# Aquila-2018_-.net
KiCad netlist of a schematic drawn in EAGLE
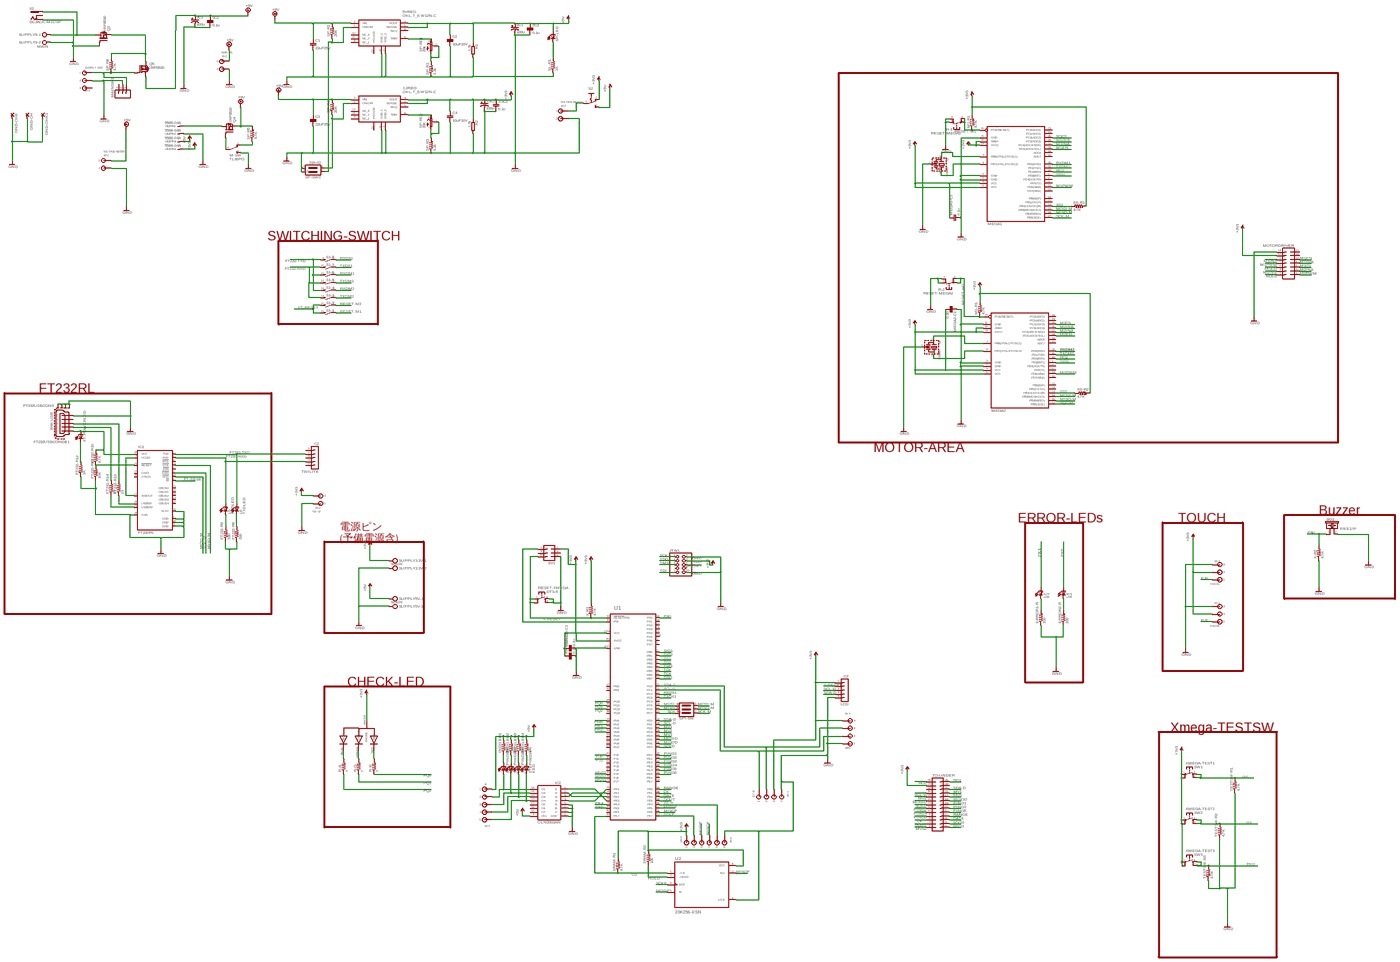
[diagram p0: schematic, sheet 1, overview]
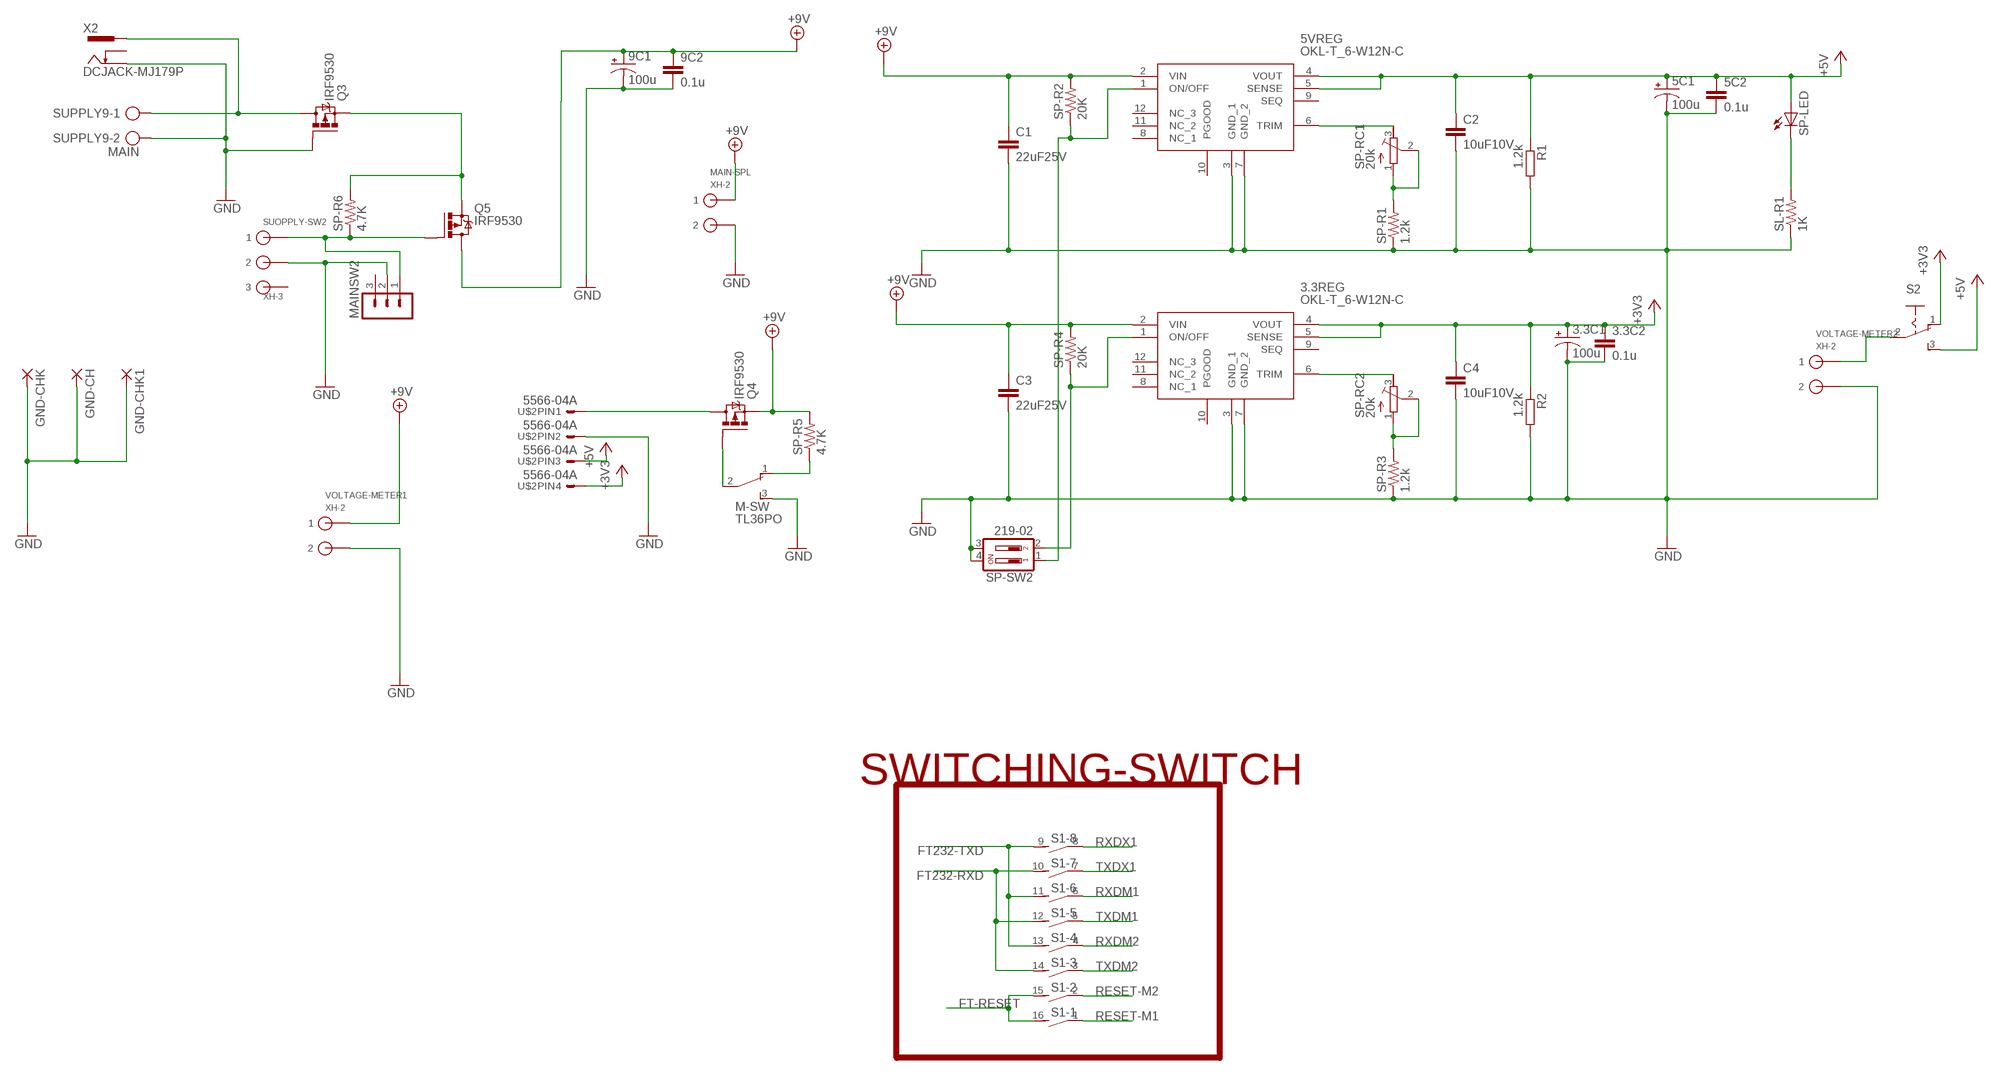
[diagram p1: schematic, sheet 1, part 1 of 5]
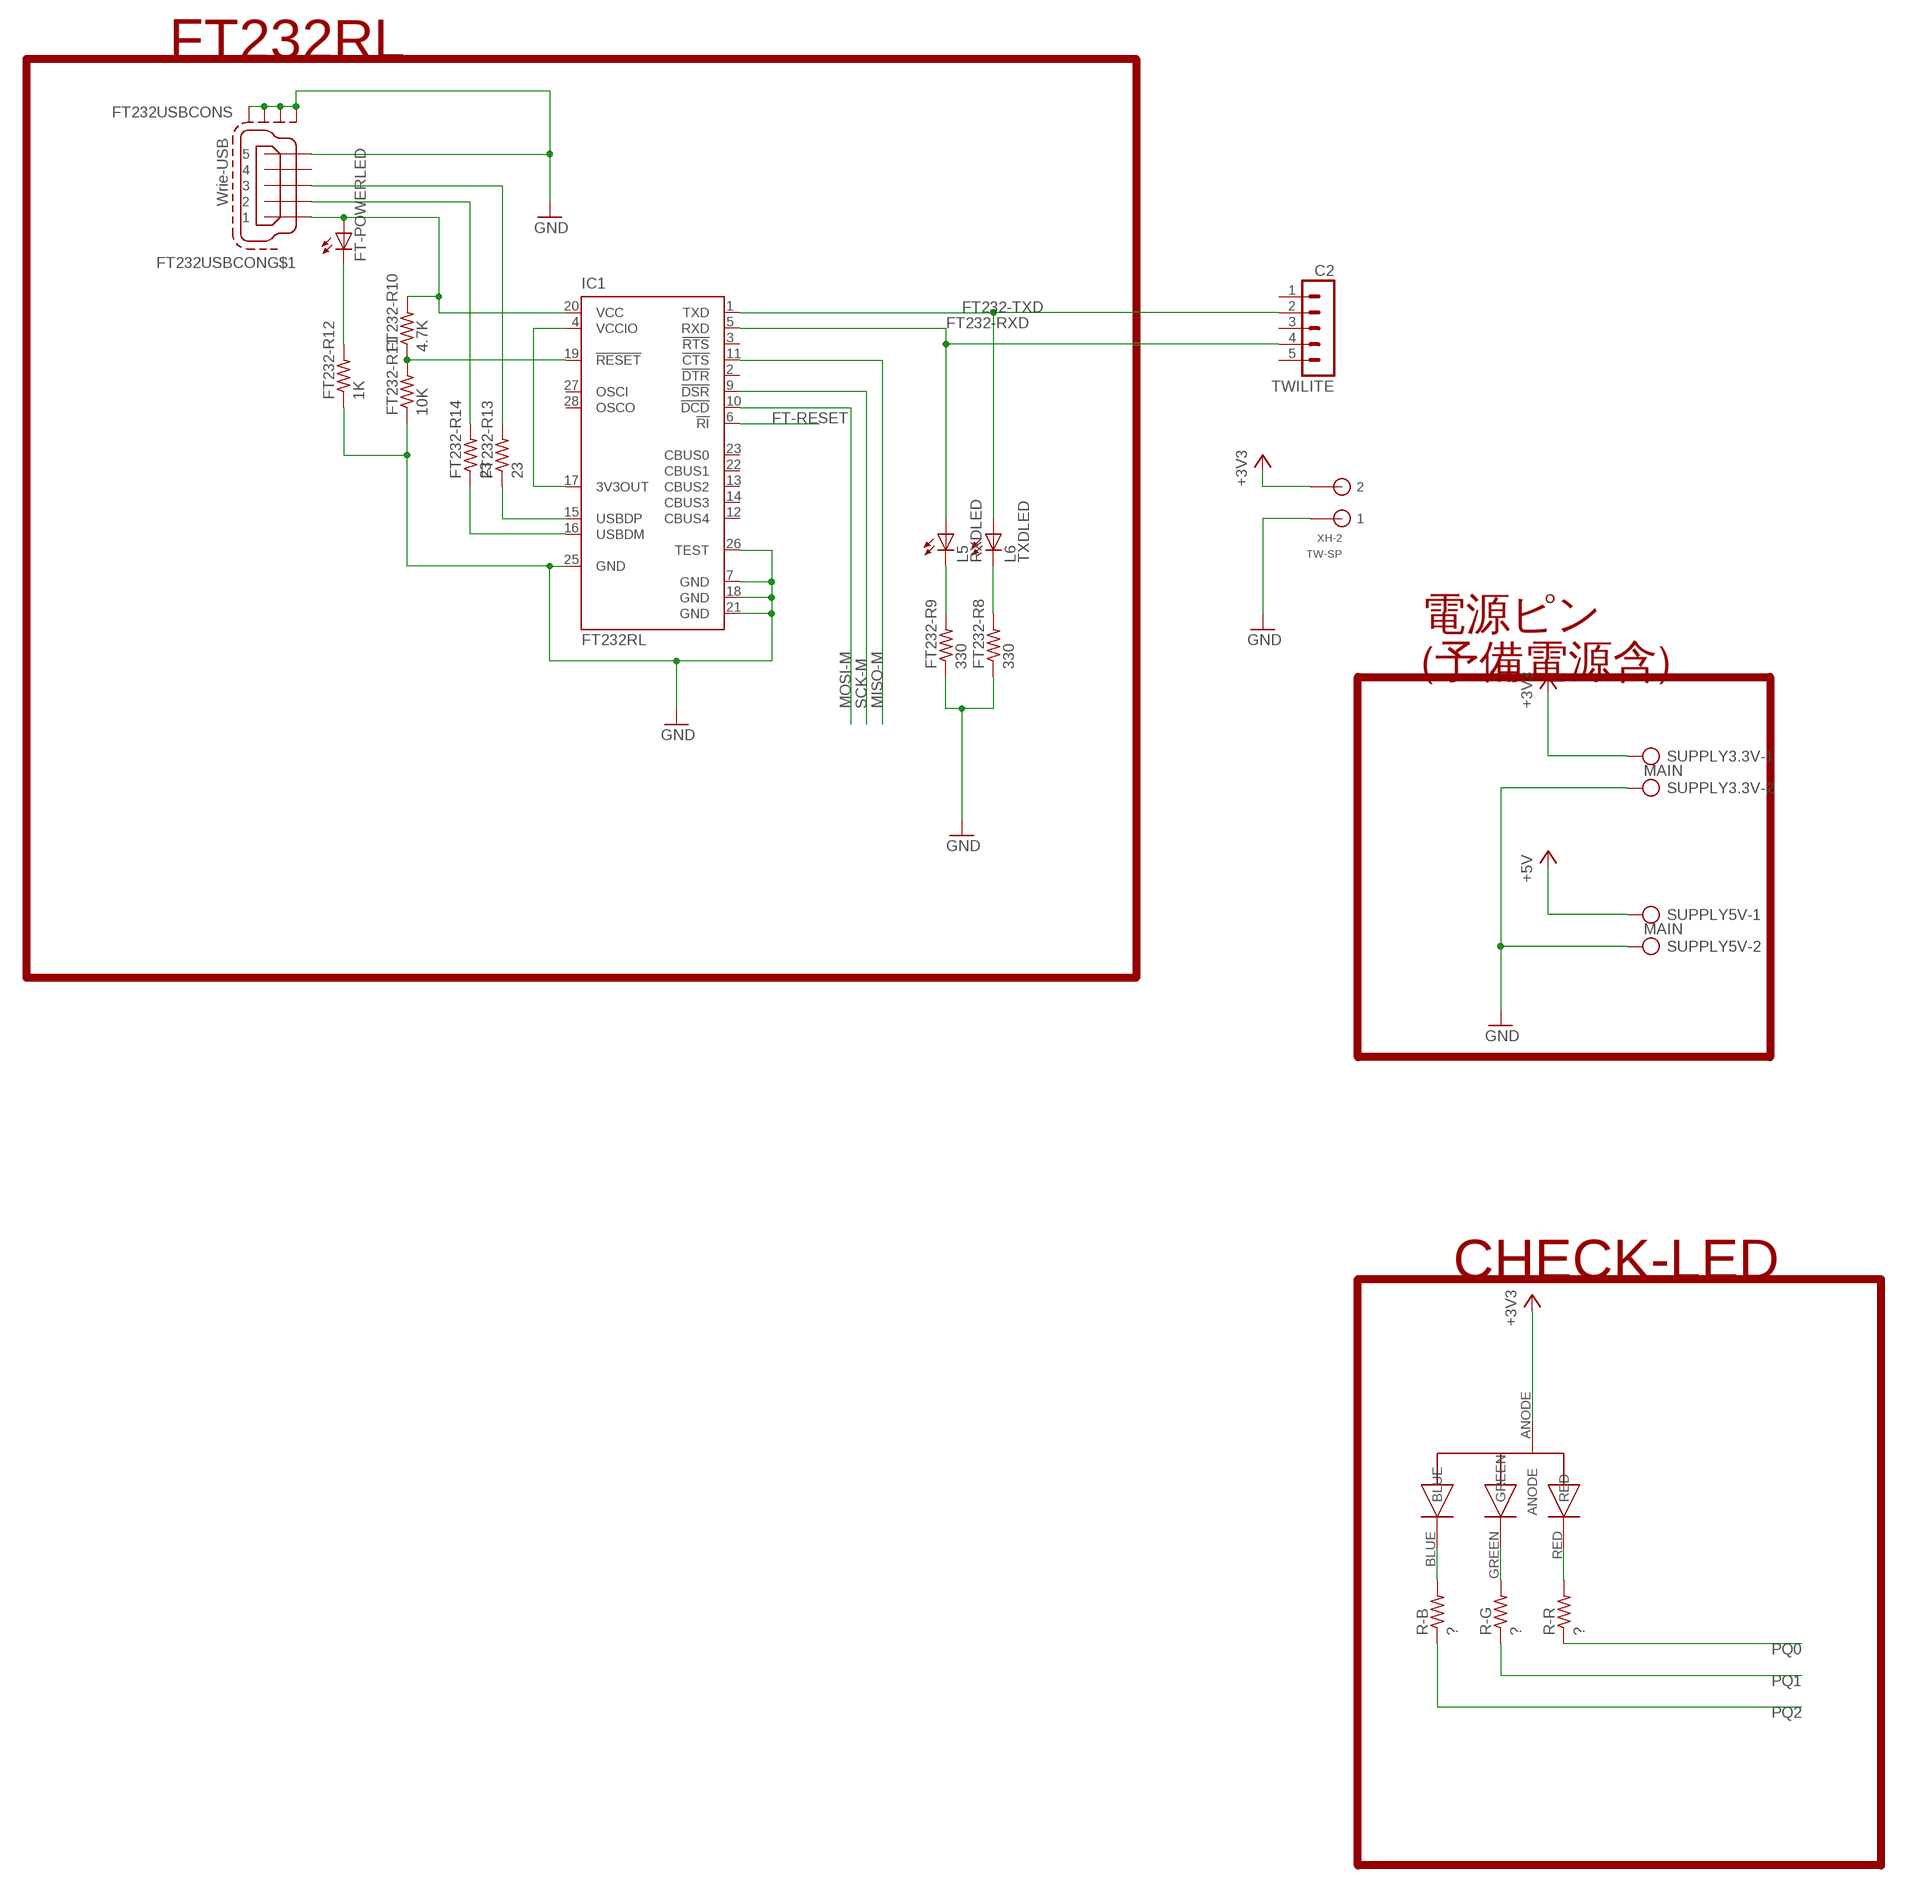
[diagram p2: schematic, sheet 1, part 2 of 5]
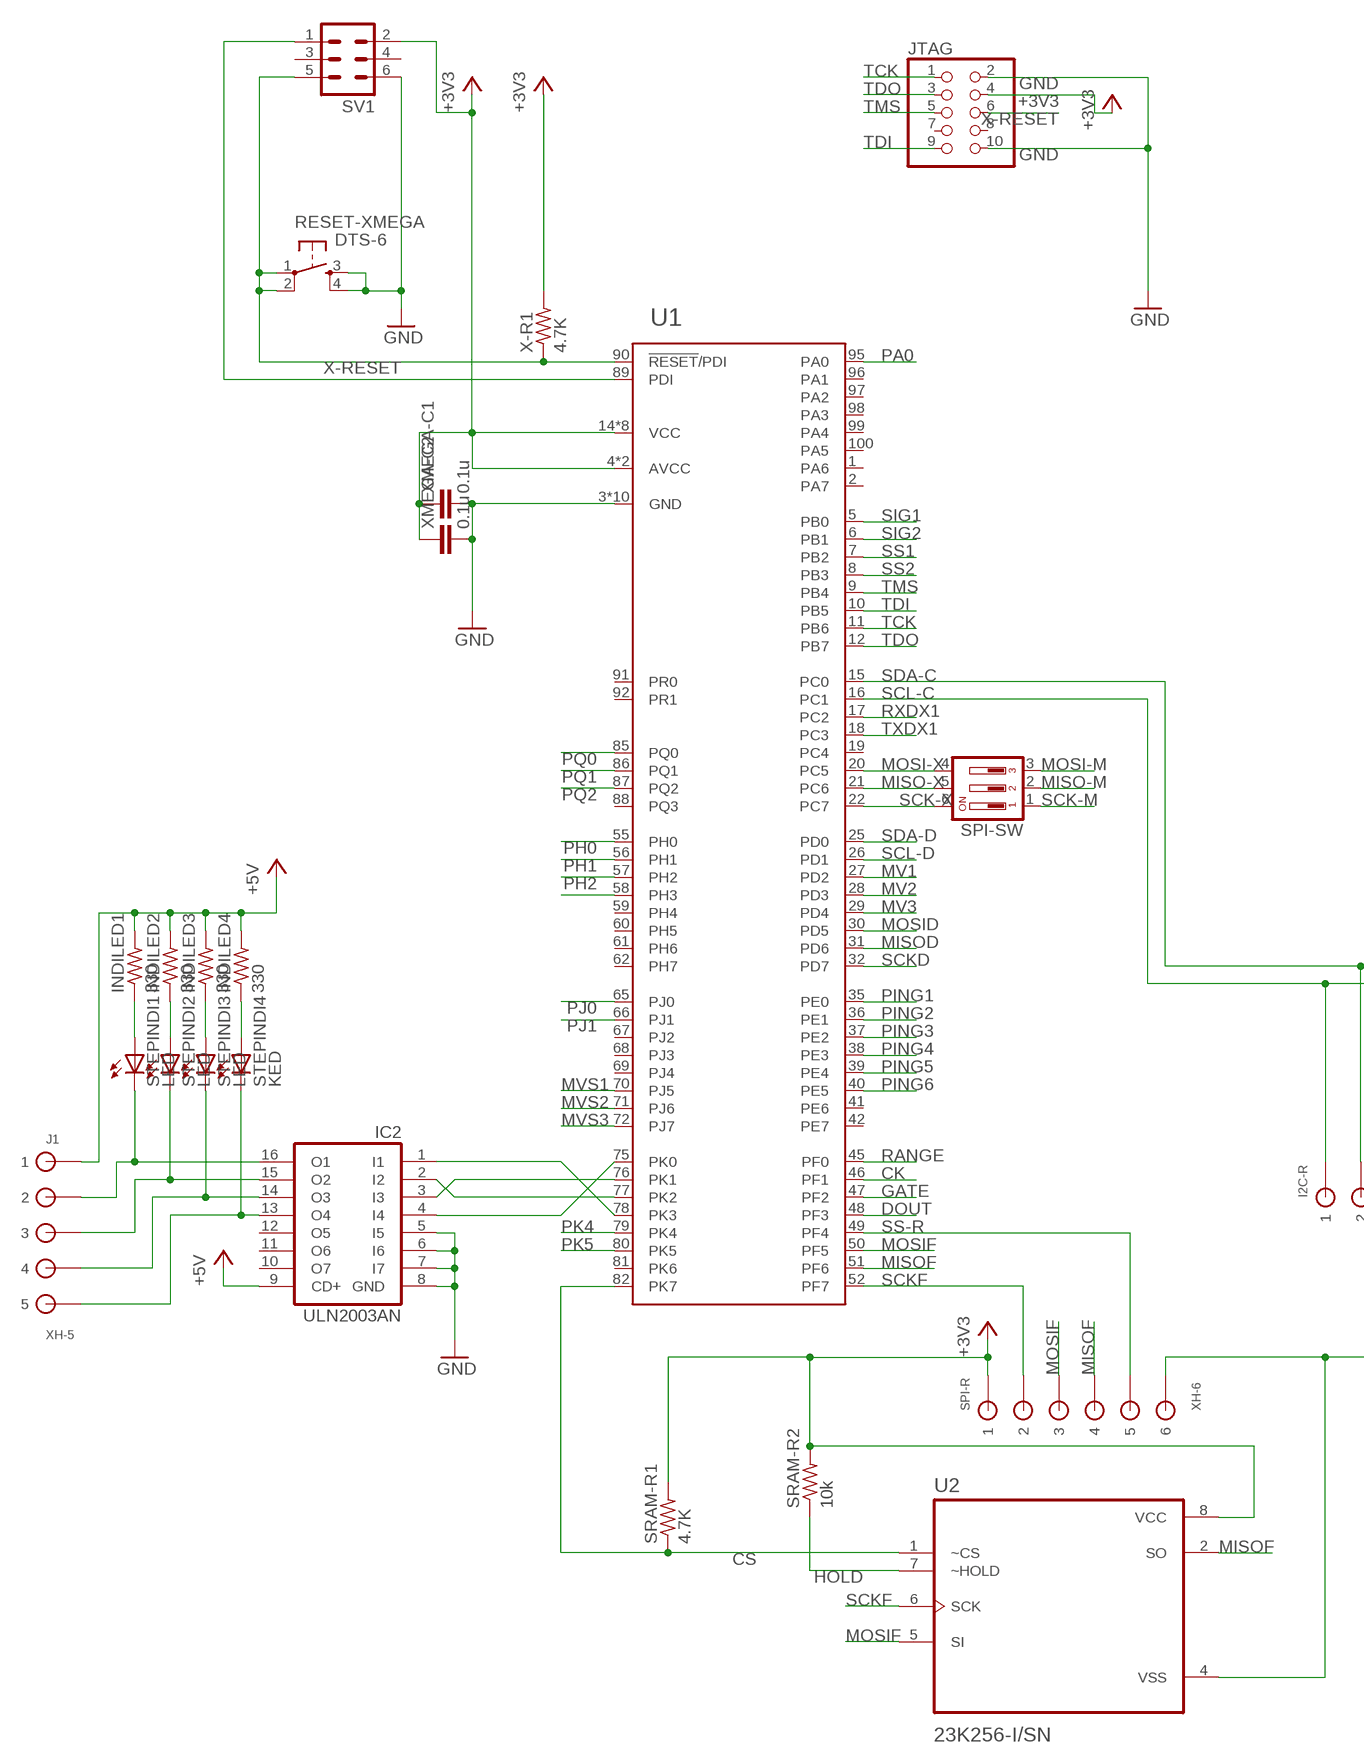
[diagram p3: schematic, sheet 1, part 3 of 5]
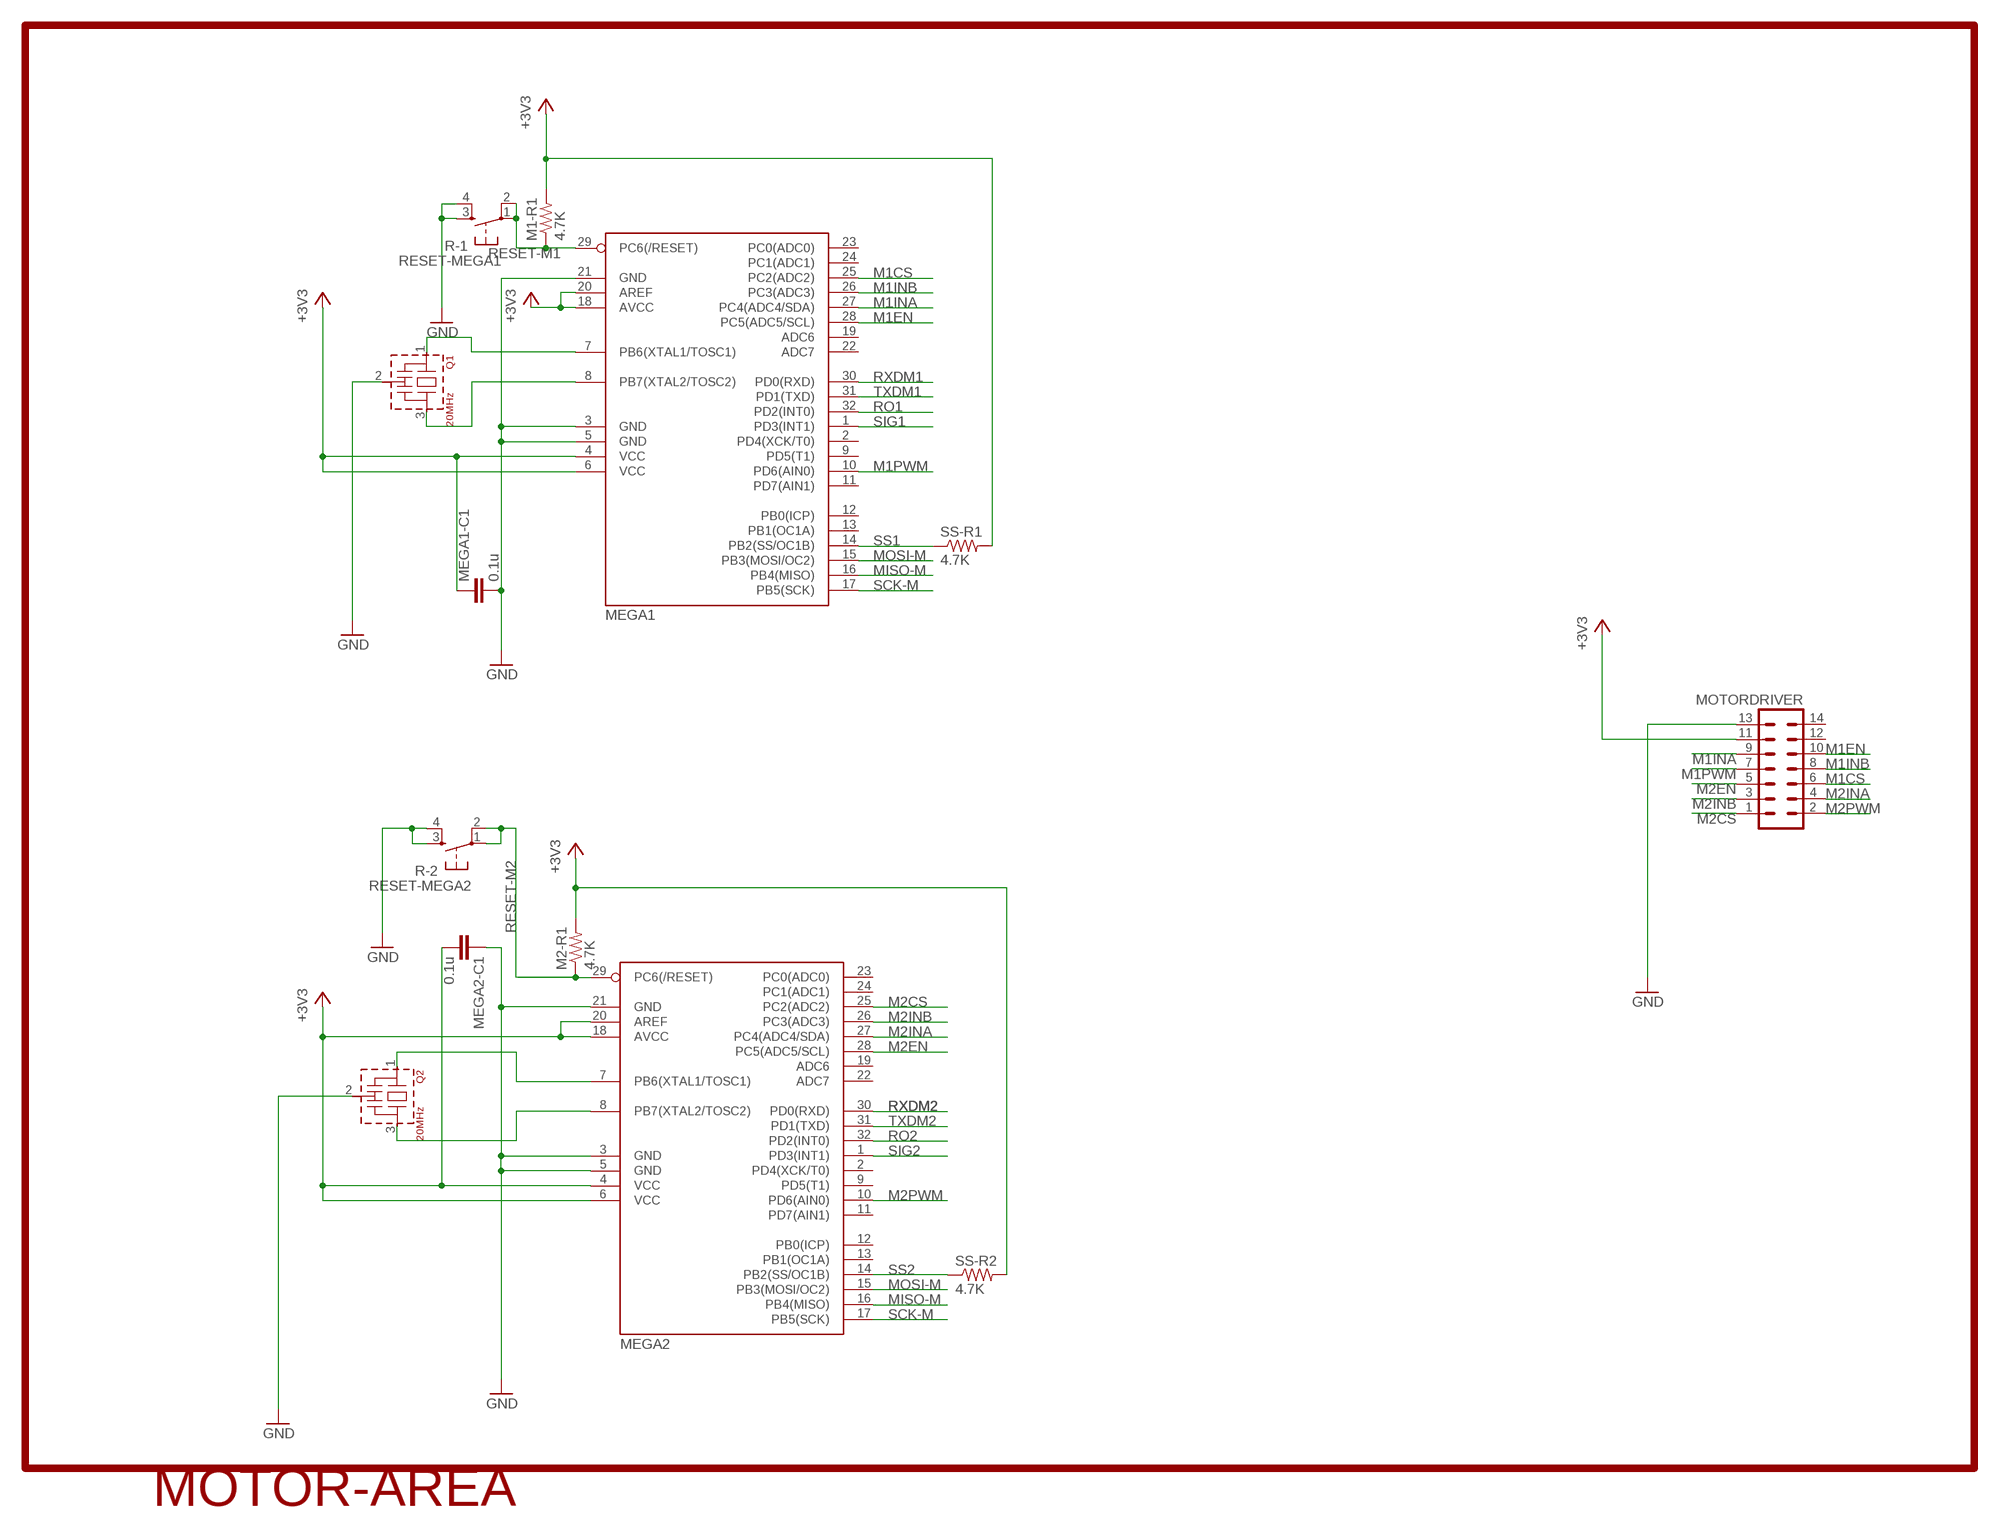
[diagram p4: schematic, sheet 1, part 4 of 5]
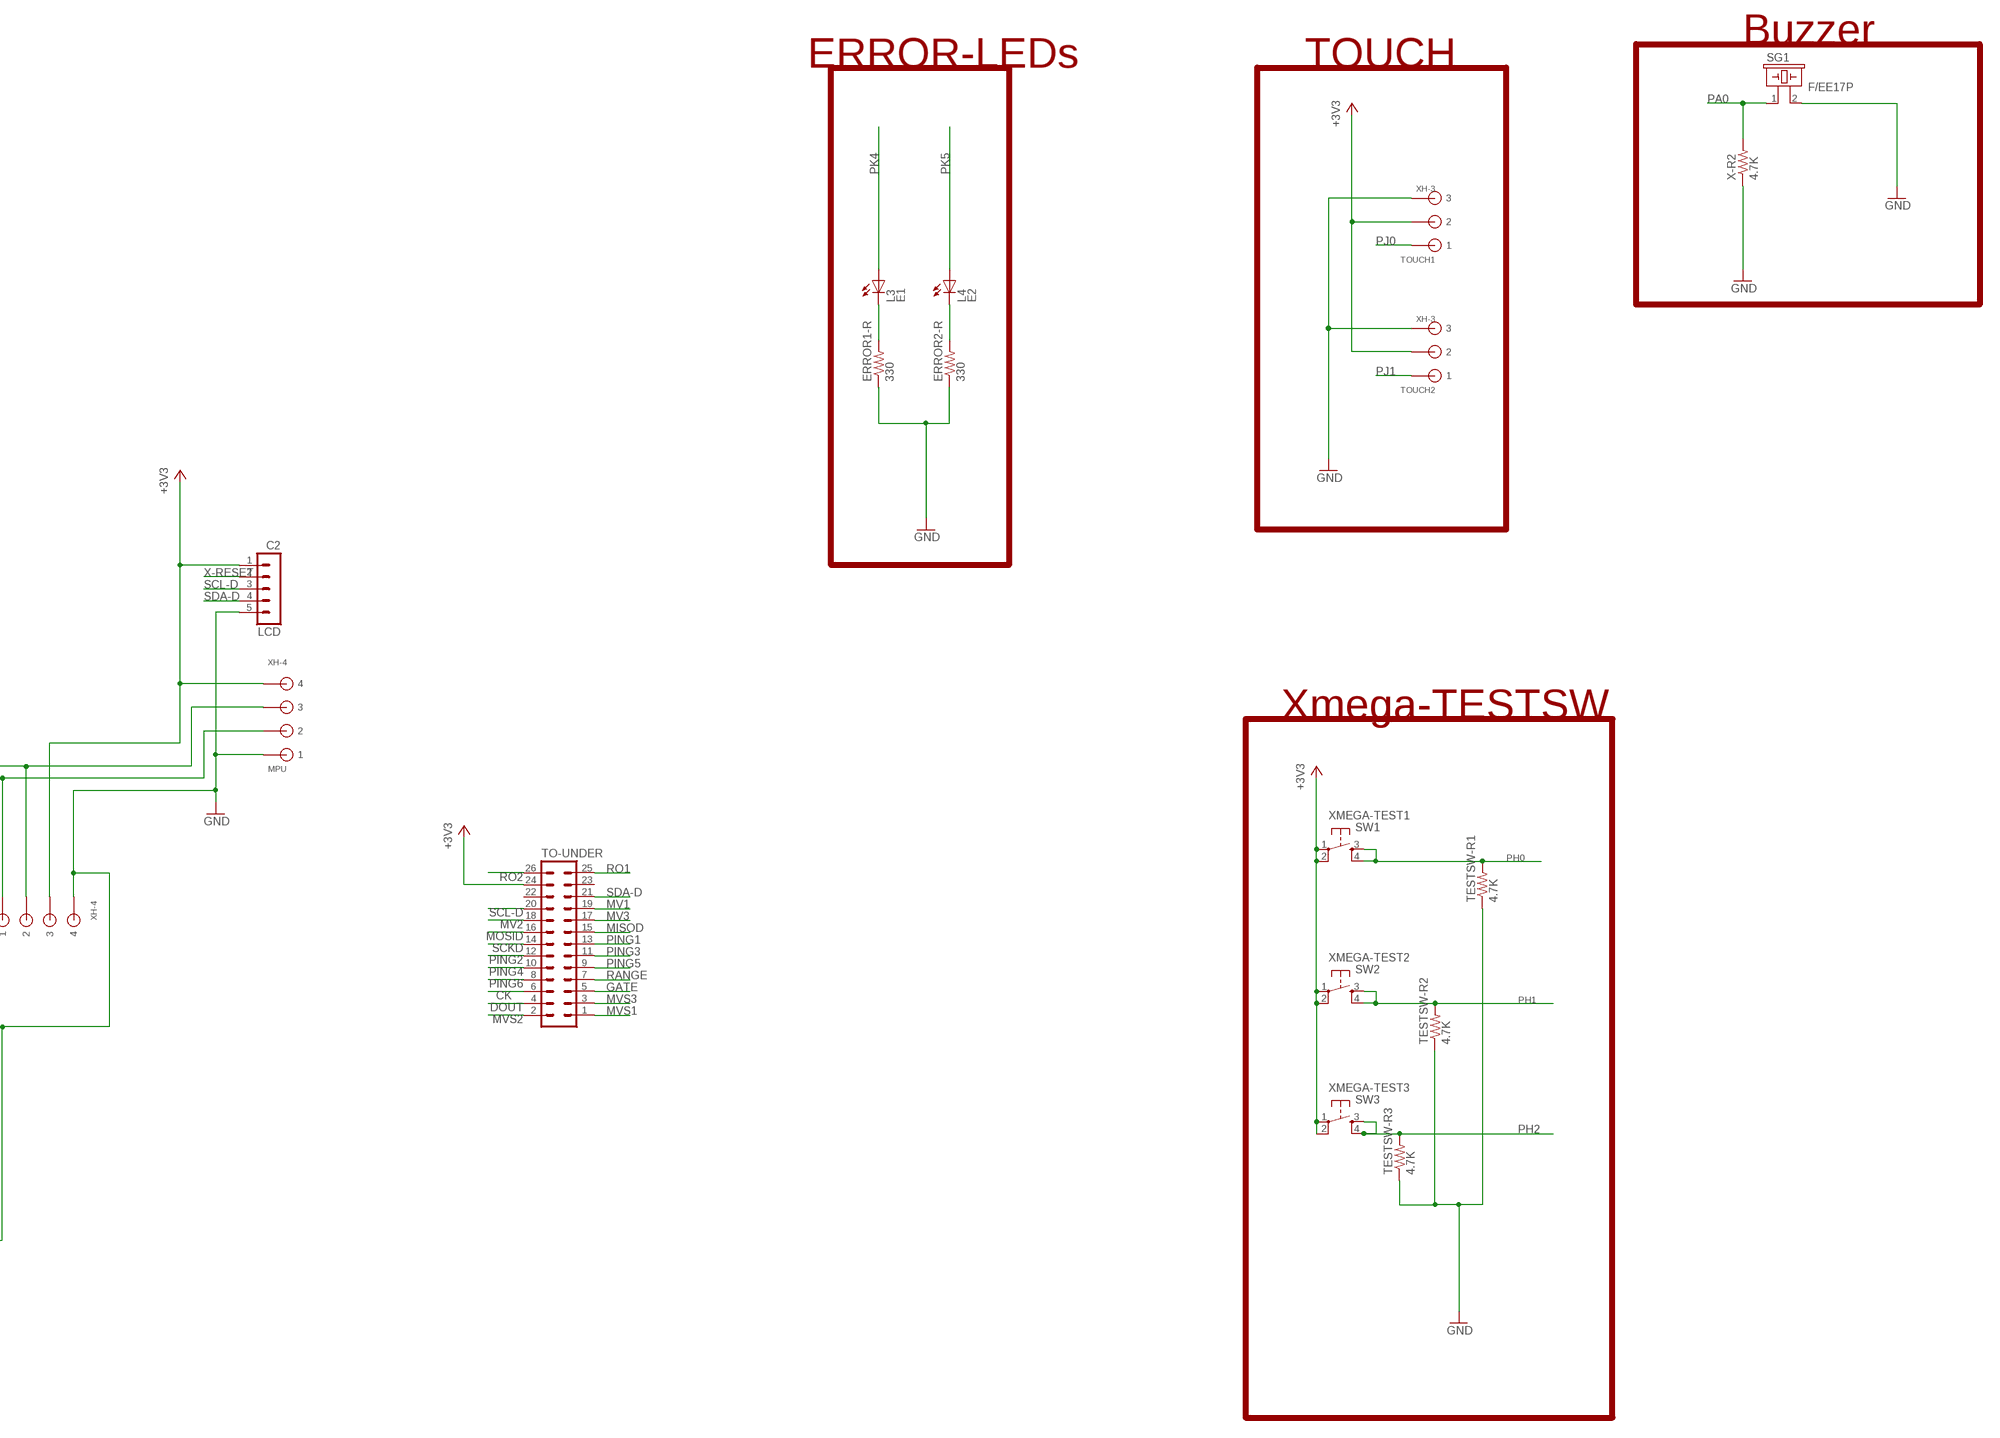
[diagram p5: schematic, sheet 1, part 5 of 5]

(export (version "E")
  (design (tool "Eeschema 10.0.6"))
  (components
    (comp (ref "3.3C1")
      (value "100u")
      (footprint "eagle-import:E2,5-6")
      (fields (field (name "SPICEPREFIX") "B"))
      (libsource (lib "eagle-import") (part "CPOL-USE2.5-6"))
    )
    (comp (ref "3.3C2")
      (value "0.1u")
      (footprint "eagle-import:C0805")
      (fields (field (name "SPICEPREFIX") "B"))
      (libsource (lib "eagle-import") (part "C-EUC0805"))
    )
    (comp (ref "3.3REG")
      (value "OKL-T_6-W12N-C")
      (footprint "eagle-import:OKL-T_3-W5")
      (fields (field (name "ARROW_PART_NUMBER") "OKL-T/6-W12N-C") (field (name "RS_PART_NUMBER") "1736944P"))
      (libsource (lib "eagle-import") (part "OKL-T_6-W12N-C"))
    )
    (comp (ref "5C1")
      (value "100u")
      (footprint "eagle-import:E2,5-6")
      (fields (field (name "SPICEPREFIX") "B"))
      (libsource (lib "eagle-import") (part "CPOL-USE2.5-6"))
    )
    (comp (ref "5C2")
      (value "0.1u")
      (footprint "eagle-import:C0805")
      (fields (field (name "SPICEPREFIX") "B"))
      (libsource (lib "eagle-import") (part "C-EUC0805"))
    )
    (comp (ref "5VREG")
      (value "OKL-T_6-W12N-C")
      (footprint "eagle-import:OKL-T_3-W5")
      (fields (field (name "ARROW_PART_NUMBER") "OKL-T/6-W12N-C") (field (name "RS_PART_NUMBER") "1736944P"))
      (libsource (lib "eagle-import") (part "OKL-T_6-W12N-C"))
    )
    (comp (ref "9C1")
      (value "100u")
      (footprint "eagle-import:E2,5-6")
      (fields (field (name "SPICEPREFIX") "B"))
      (libsource (lib "eagle-import") (part "CPOL-USE2.5-6"))
    )
    (comp (ref "9C2")
      (value "0.1u")
      (footprint "eagle-import:C0805")
      (fields (field (name "SPICEPREFIX") "B"))
      (libsource (lib "eagle-import") (part "C-EUC0805"))
    )
    (comp (ref "C1")
      (value "22uF25V")
      (footprint "eagle-import:C2012")
      (libsource (lib "eagle-import") (part "resistor_348_C-EUC2012"))
    )
    (comp (ref "C2")
      (value "10uF10V")
      (footprint "eagle-import:C2012")
      (libsource (lib "eagle-import") (part "resistor_348_C-EUC2012"))
    )
    (comp (ref "C3")
      (value "22uF25V")
      (footprint "eagle-import:C2012")
      (libsource (lib "eagle-import") (part "resistor_348_C-EUC2012"))
    )
    (comp (ref "C4")
      (value "10uF10V")
      (footprint "eagle-import:C2012")
      (libsource (lib "eagle-import") (part "resistor_348_C-EUC2012"))
    )
    (comp (ref "CHECKLED")
      (value "OSTA71A1D-A")
      (footprint "eagle-import:OSTA71A1D-A")
      (libsource (lib "eagle-import") (part "OSTA71A1D-A"))
    )
    (comp (ref "ERROR1-R")
      (value "330")
      (footprint "eagle-import:R0805")
      (libsource (lib "eagle-import") (part "R-US_R0805"))
    )
    (comp (ref "ERROR2-R")
      (value "330")
      (footprint "eagle-import:R0805")
      (libsource (lib "eagle-import") (part "R-US_R0805"))
    )
    (comp (ref "FT-POWERLED")
      (value "LEDCHIPLED_0805")
      (footprint "eagle-import:CHIPLED_0805")
      (libsource (lib "eagle-import") (part "led_LEDCHIPLED_0805"))
    )
    (comp (ref "FT232-R8")
      (value "330")
      (footprint "eagle-import:R0805")
      (libsource (lib "eagle-import") (part "R-US_R0805"))
    )
    (comp (ref "FT232-R9")
      (value "330")
      (footprint "eagle-import:R0805")
      (libsource (lib "eagle-import") (part "R-US_R0805"))
    )
    (comp (ref "FT232-R10")
      (value "4.7K")
      (footprint "eagle-import:R0805")
      (libsource (lib "eagle-import") (part "R-US_R0805"))
    )
    (comp (ref "FT232-R11")
      (value "10K")
      (footprint "eagle-import:R0805")
      (libsource (lib "eagle-import") (part "R-US_R0805"))
    )
    (comp (ref "FT232-R12")
      (value "1K")
      (footprint "eagle-import:R0805")
      (libsource (lib "eagle-import") (part "R-US_R0805"))
    )
    (comp (ref "FT232-R13")
      (value "23")
      (footprint "eagle-import:R0805")
      (libsource (lib "eagle-import") (part "R-US_R0805"))
    )
    (comp (ref "FT232-R14")
      (value "23")
      (footprint "eagle-import:R0805")
      (libsource (lib "eagle-import") (part "R-US_R0805"))
    )
    (comp (ref "FT232USBCON")
      (value "Wrie-USB")
      (footprint "eagle-import:32005-201")
      (libsource (lib "eagle-import") (part "MINI-USB-SCHIELD-32005-201"))
    )
    (comp (ref "GND-CH")
      (value "SMD5")
      (footprint "eagle-import:SMD2,54-5,08")
      (libsource (lib "eagle-import") (part "SMD5"))
    )
    (comp (ref "GND-CHK")
      (value "2,15/1,0")
      (footprint "eagle-import:2,15_1,0")
      (libsource (lib "eagle-import") (part "2,15/1,0"))
    )
    (comp (ref "GND-CHK1")
      (value "2,15/1,0")
      (footprint "eagle-import:2,15_1,0")
      (libsource (lib "eagle-import") (part "2,15/1,0"))
    )
    (comp (ref "I2C-R")
      (value "XH-4")
      (footprint "eagle-import:CON4")
      (libsource (lib "eagle-import") (part "XH-4"))
    )
    (comp (ref "IC1")
      (value "FT232RL")
      (footprint "eagle-import:SSOP28")
      (libsource (lib "eagle-import") (part "FT232RL"))
    )
    (comp (ref "IC2")
      (value "ULN2003AN")
      (footprint "eagle-import:DIL16")
      (fields (field (name "MF") "STMicroelectronics") (field (name "MP") "ULN2003A"))
      (libsource (lib "eagle-import") (part "ULN2003AN"))
    )
    (comp (ref "INDILED1")
      (value "330")
      (footprint "eagle-import:R0805")
      (libsource (lib "eagle-import") (part "R-US_R0805"))
    )
    (comp (ref "INDILED2")
      (value "330")
      (footprint "eagle-import:R0805")
      (libsource (lib "eagle-import") (part "R-US_R0805"))
    )
    (comp (ref "INDILED3")
      (value "330")
      (footprint "eagle-import:R0805")
      (libsource (lib "eagle-import") (part "R-US_R0805"))
    )
    (comp (ref "INDILED4")
      (value "330")
      (footprint "eagle-import:R0805")
      (libsource (lib "eagle-import") (part "R-US_R0805"))
    )
    (comp (ref "J1")
      (value "XH-5")
      (footprint "eagle-import:CON5")
      (libsource (lib "eagle-import") (part "XH-5"))
    )
    (comp (ref "JTAG")
      (value "20021221-00010C4LF")
      (footprint "eagle-import:20021221-00010C4LF")
      (libsource (lib "eagle-import") (part "20021221-00010C4LF"))
    )
    (comp (ref "L3")
      (value "E1")
      (footprint "eagle-import:LED5MM")
      (libsource (lib "eagle-import") (part "LED5MM"))
    )
    (comp (ref "L4")
      (value "E2")
      (footprint "eagle-import:LED5MM")
      (libsource (lib "eagle-import") (part "LED5MM"))
    )
    (comp (ref "L5")
      (value "RXDLED")
      (footprint "eagle-import:CHIPLED_0805")
      (libsource (lib "eagle-import") (part "led_LEDCHIPLED_0805"))
    )
    (comp (ref "L6")
      (value "TXDLED")
      (footprint "eagle-import:CHIPLED_0805")
      (libsource (lib "eagle-import") (part "led_LEDCHIPLED_0805"))
    )
    (comp (ref "LCD")
      (value "C2")
      (footprint "eagle-import:MA05-1")
      (libsource (lib "eagle-import") (part "MA05-1"))
    )
    (comp (ref "M-SW")
      (value "TL36PO")
      (footprint "eagle-import:TL3XPO")
      (libsource (lib "eagle-import") (part "TL36PO"))
    )
    (comp (ref "M1-R1")
      (value "4.7K")
      (footprint "eagle-import:R0805")
      (libsource (lib "eagle-import") (part "R-US_R0805"))
    )
    (comp (ref "M2-R1")
      (value "4.7K")
      (footprint "eagle-import:R0805")
      (libsource (lib "eagle-import") (part "R-US_R0805"))
    )
    (comp (ref "MAIN-SPL")
      (value "XH-2")
      (footprint "eagle-import:CON2")
      (libsource (lib "eagle-import") (part "forprint_XH-2"))
    )
    (comp (ref "MAINSW2")
      (value "MA03-1")
      (footprint "eagle-import:MA03-1")
      (libsource (lib "eagle-import") (part "MA03-1"))
    )
    (comp (ref "MEGA1")
      (value "MEGA8-AI")
      (footprint "eagle-import:TQFP32-08")
      (fields (field (name "MPN") "ATMEGA8-16AU"))
      (libsource (lib "eagle-import") (part "MEGA8-AI"))
    )
    (comp (ref "MEGA1-C1")
      (value "0.1u")
      (footprint "eagle-import:C0805")
      (libsource (lib "eagle-import") (part "C-EUC0805"))
    )
    (comp (ref "MEGA2")
      (value "MEGA8-AI")
      (footprint "eagle-import:TQFP32-08")
      (fields (field (name "MPN") "ATMEGA8-16AU"))
      (libsource (lib "eagle-import") (part "MEGA8-AI"))
    )
    (comp (ref "MEGA2-C1")
      (value "0.1u")
      (footprint "eagle-import:C0805")
      (libsource (lib "eagle-import") (part "C-EUC0805"))
    )
    (comp (ref "MOTORDRIVER")
      (value "ML14")
      (footprint "eagle-import:ML14")
      (libsource (lib "eagle-import") (part "ML14"))
    )
    (comp (ref "MPU")
      (value "XH-4")
      (footprint "eagle-import:CON4")
      (libsource (lib "eagle-import") (part "XH-4"))
    )
    (comp (ref "Q1")
      (value "20MHz")
      (footprint "eagle-import:CSTLS_X")
      (libsource (lib "eagle-import") (part "CSTLS_X"))
    )
    (comp (ref "Q2")
      (value "20MHz")
      (footprint "eagle-import:CSTLS_X")
      (libsource (lib "eagle-import") (part "CSTLS_X"))
    )
    (comp (ref "Q3")
      (value "IRF9530")
      (footprint "eagle-import:TO220BV")
      (libsource (lib "eagle-import") (part "IRF9530"))
    )
    (comp (ref "Q4")
      (value "IRF9530")
      (footprint "eagle-import:TO220BV")
      (libsource (lib "eagle-import") (part "IRF9530"))
    )
    (comp (ref "Q5")
      (value "IRF9530")
      (footprint "eagle-import:TO220BV")
      (libsource (lib "eagle-import") (part "IRF9530"))
    )
    (comp (ref "R-B")
      (value "?")
      (footprint "eagle-import:R0805")
      (libsource (lib "eagle-import") (part "R-US_R0805"))
    )
    (comp (ref "R-G")
      (value "?")
      (footprint "eagle-import:R0805")
      (libsource (lib "eagle-import") (part "R-US_R0805"))
    )
    (comp (ref "R-R")
      (value "?")
      (footprint "eagle-import:R0805")
      (libsource (lib "eagle-import") (part "R-US_R0805"))
    )
    (comp (ref "R1")
      (value "1.2k")
      (footprint "eagle-import:0204_7")
      (libsource (lib "eagle-import") (part "R-EU_0204/7"))
    )
    (comp (ref "R2")
      (value "1.2k")
      (footprint "eagle-import:0204_7")
      (libsource (lib "eagle-import") (part "R-EU_0204/7"))
    )
    (comp (ref "RESET-MEGA1")
      (value "R-1")
      (footprint "eagle-import:DTS-6")
      (libsource (lib "eagle-import") (part "DTS-6"))
    )
    (comp (ref "RESET-MEGA2")
      (value "R-2")
      (footprint "eagle-import:DTS-6")
      (libsource (lib "eagle-import") (part "DTS-6"))
    )
    (comp (ref "RESET-XMEGA")
      (value "DTS-6")
      (footprint "eagle-import:DTS-6")
      (libsource (lib "eagle-import") (part "DTS-6"))
    )
    (comp (ref "S1")
      (value "DIP08S")
      (footprint "eagle-import:DIP08S")
      (libsource (lib "eagle-import") (part "DIP08S"))
    )
    (comp (ref "S2")
      (value "M251")
      (footprint "eagle-import:M251")
      (libsource (lib "eagle-import") (part "M251"))
    )
    (comp (ref "SG1")
      (value "F/EE17P")
      (footprint "eagle-import:F_EE17P")
      (libsource (lib "eagle-import") (part "F/EE17P"))
    )
    (comp (ref "SL-R1")
      (value "1K")
      (footprint "eagle-import:R0805")
      (libsource (lib "eagle-import") (part "R-US_R0805"))
    )
    (comp (ref "SP-LED")
      (value "LEDCHIPLED_0805")
      (footprint "eagle-import:CHIPLED_0805")
      (libsource (lib "eagle-import") (part "led_LEDCHIPLED_0805"))
    )
    (comp (ref "SP-R1")
      (value "1.2k")
      (footprint "eagle-import:R0805")
      (libsource (lib "eagle-import") (part "R-US_R0805"))
    )
    (comp (ref "SP-R2")
      (value "20K")
      (footprint "eagle-import:R0805")
      (libsource (lib "eagle-import") (part "R-US_R0805"))
    )
    (comp (ref "SP-R3")
      (value "1.2k")
      (footprint "eagle-import:R0805")
      (libsource (lib "eagle-import") (part "R-US_R0805"))
    )
    (comp (ref "SP-R4")
      (value "20K")
      (footprint "eagle-import:R0805")
      (libsource (lib "eagle-import") (part "R-US_R0805"))
    )
    (comp (ref "SP-R5")
      (value "4.7K")
      (footprint "eagle-import:R0805")
      (libsource (lib "eagle-import") (part "R-US_R0805"))
    )
    (comp (ref "SP-R6")
      (value "4.7K")
      (footprint "eagle-import:R0805")
      (libsource (lib "eagle-import") (part "R-US_R0805"))
    )
    (comp (ref "SP-RC1")
      (value "20k")
      (footprint "eagle-import:RTRIM3296W")
      (libsource (lib "eagle-import") (part "R-TRIMM3296W"))
    )
    (comp (ref "SP-RC2")
      (value "20k")
      (footprint "eagle-import:RTRIM3296W")
      (libsource (lib "eagle-import") (part "R-TRIMM3296W"))
    )
    (comp (ref "SP-SW2")
      (value "219-02")
      (footprint "eagle-import:CTS-219-02")
      (libsource (lib "eagle-import") (part "219-02"))
    )
    (comp (ref "SPI-R")
      (value "XH-6")
      (footprint "eagle-import:CON6")
      (libsource (lib "eagle-import") (part "XH-6"))
    )
    (comp (ref "SPI-SW")
      (value "DIP03YL")
      (footprint "eagle-import:DIP03YL")
      (libsource (lib "eagle-import") (part "DIP03YL"))
    )
    (comp (ref "SRAM-R1")
      (value "4.7K")
      (footprint "eagle-import:R0805")
      (libsource (lib "eagle-import") (part "R-US_R0805"))
    )
    (comp (ref "SRAM-R2")
      (value "10k")
      (footprint "eagle-import:R0805")
      (libsource (lib "eagle-import") (part "R-US_R0805"))
    )
    (comp (ref "SS-R1")
      (value "4.7K")
      (footprint "eagle-import:R0805")
      (libsource (lib "eagle-import") (part "R-US_R0805"))
    )
    (comp (ref "SS-R2")
      (value "4.7K")
      (footprint "eagle-import:R0805")
      (libsource (lib "eagle-import") (part "R-US_R0805"))
    )
    (comp (ref "STEPINDI1")
      (value "LED")
      (footprint "eagle-import:CHIPLED_0805")
      (libsource (lib "eagle-import") (part "led_LEDCHIPLED_0805"))
    )
    (comp (ref "STEPINDI2")
      (value "LED")
      (footprint "eagle-import:CHIPLED_0805")
      (libsource (lib "eagle-import") (part "led_LEDCHIPLED_0805"))
    )
    (comp (ref "STEPINDI3")
      (value "LED")
      (footprint "eagle-import:CHIPLED_0805")
      (libsource (lib "eagle-import") (part "led_LEDCHIPLED_0805"))
    )
    (comp (ref "STEPINDI4")
      (value "KED")
      (footprint "eagle-import:CHIPLED_0805")
      (libsource (lib "eagle-import") (part "led_LEDCHIPLED_0805"))
    )
    (comp (ref "SUOPPLY-SW2")
      (value "XH-3")
      (footprint "eagle-import:CON3")
      (libsource (lib "eagle-import") (part "XH-3"))
    )
    (comp (ref "SUPPLY3.3V")
      (value "MAIN")
      (footprint "eagle-import:AK500_2")
      (libsource (lib "eagle-import") (part "AK500/2"))
    )
    (comp (ref "SUPPLY5V")
      (value "MAIN")
      (footprint "eagle-import:AK500_2")
      (libsource (lib "eagle-import") (part "AK500/2"))
    )
    (comp (ref "SUPPLY9")
      (value "MAIN")
      (footprint "eagle-import:AK500_2")
      (libsource (lib "eagle-import") (part "AK500/2"))
    )
    (comp (ref "SV1")
      (value "ML6")
      (footprint "eagle-import:ML6")
      (libsource (lib "eagle-import") (part "ML6"))
    )
    (comp (ref "TESTSW-R1")
      (value "4.7K")
      (footprint "eagle-import:R0805")
      (libsource (lib "eagle-import") (part "R-US_R0805"))
    )
    (comp (ref "TESTSW-R2")
      (value "4.7K")
      (footprint "eagle-import:R0805")
      (libsource (lib "eagle-import") (part "R-US_R0805"))
    )
    (comp (ref "TESTSW-R3")
      (value "4.7K")
      (footprint "eagle-import:R0805")
      (libsource (lib "eagle-import") (part "R-US_R0805"))
    )
    (comp (ref "TO-UNDER")
      (value "ML26")
      (footprint "eagle-import:ML26")
      (libsource (lib "eagle-import") (part "ML26"))
    )
    (comp (ref "TOUCH1")
      (value "XH-3")
      (footprint "eagle-import:CON3")
      (libsource (lib "eagle-import") (part "XH-3"))
    )
    (comp (ref "TOUCH2")
      (value "XH-3")
      (footprint "eagle-import:CON3")
      (libsource (lib "eagle-import") (part "XH-3"))
    )
    (comp (ref "TW-SP")
      (value "XH-2")
      (footprint "eagle-import:CON2")
      (libsource (lib "eagle-import") (part "XH-2"))
    )
    (comp (ref "TWILITE")
      (value "C2")
      (footprint "eagle-import:MA05-1")
      (libsource (lib "eagle-import") (part "MA05-1"))
    )
    (comp (ref "U$2")
      (value "5566-04A")
      (footprint "eagle-import:5566-04A")
      (libsource (lib "eagle-import") (part "5566-04A"))
    )
    (comp (ref "U1")
      (value "ATXMEGA128A1U-AU")
      (footprint "eagle-import:TQFP-100A-100")
      (libsource (lib "eagle-import") (part "ATXMEGA128A1U-AU"))
    )
    (comp (ref "U2")
      (value "23K256-I/SN")
      (footprint "eagle-import:SOIC127P600X175-8N")
      (fields (field (name "MF") "Microchip"))
      (libsource (lib "eagle-import") (part "23K256-I/SN"))
    )
    (comp (ref "VOLTAGE-METER1")
      (value "XH-2")
      (footprint "eagle-import:CON2")
      (libsource (lib "eagle-import") (part "forprint_XH-2"))
    )
    (comp (ref "VOLTAGE-METER2")
      (value "XH-2")
      (footprint "eagle-import:CON2")
      (libsource (lib "eagle-import") (part "forprint_XH-2"))
    )
    (comp (ref "X-R1")
      (value "4.7K")
      (footprint "eagle-import:R0805")
      (libsource (lib "eagle-import") (part "R-US_R0805"))
    )
    (comp (ref "X-R2")
      (value "4.7K")
      (footprint "eagle-import:R0805")
      (libsource (lib "eagle-import") (part "R-US_R0805"))
    )
    (comp (ref "X2")
      (value "DCJACK-MJ179P")
      (footprint "eagle-import:MJ-179P")
      (libsource (lib "eagle-import") (part "DCJACK-MJ179P"))
    )
    (comp (ref "XMEGA-C1")
      (value "0.1u")
      (footprint "eagle-import:C0805")
      (libsource (lib "eagle-import") (part "C-EUC0805"))
    )
    (comp (ref "XMEGA-C2")
      (value "0.1u")
      (footprint "eagle-import:C0805")
      (libsource (lib "eagle-import") (part "C-EUC0805"))
    )
    (comp (ref "XMEGA-TEST1")
      (value "SW1")
      (footprint "eagle-import:DTS-6")
      (libsource (lib "eagle-import") (part "DTS-6"))
    )
    (comp (ref "XMEGA-TEST2")
      (value "SW2")
      (footprint "eagle-import:DTS-6")
      (libsource (lib "eagle-import") (part "DTS-6"))
    )
    (comp (ref "XMEGA-TEST3")
      (value "SW3")
      (footprint "eagle-import:DTS-6")
      (libsource (lib "eagle-import") (part "DTS-6"))
    )
  )
  (nets
    (net (code "1") (name "+3V3") (class "Default")
      (node (ref "3.3C1") (pin "+") (pinfunction "+_+") (pintype "passive"))
      (node (ref "3.3C2") (pin "1") (pinfunction "1_1") (pintype "passive"))
      (node (ref "3.3REG") (pin "4") (pinfunction "VOUT_4") (pintype "bidirectional"))
      (node (ref "3.3REG") (pin "5") (pinfunction "SENSE_5") (pintype "bidirectional"))
      (node (ref "C4") (pin "1") (pinfunction "1_1") (pintype "passive"))
      (node (ref "CHECKLED") (pin "ANODE") (pinfunction "ANODE_ANODE") (pintype "bidirectional"))
      (node (ref "I2C-R") (pin "P$3") (pinfunction "3_P$3") (pintype "bidirectional"))
      (node (ref "JTAG") (pin "4") (pinfunction "4_4") (pintype "passive"))
      (node (ref "LCD") (pin "1") (pinfunction "1_1") (pintype "passive"))
      (node (ref "M1-R1") (pin "2") (pinfunction "2_2") (pintype "passive"))
      (node (ref "M2-R1") (pin "2") (pinfunction "2_2") (pintype "passive"))
      (node (ref "MEGA1") (pin "18") (pinfunction "AVCC_18") (pintype "power_in"))
      (node (ref "MEGA1") (pin "20") (pinfunction "AREF_20") (pintype "passive"))
      (node (ref "MEGA1") (pin "4") (pinfunction "VCC_4") (pintype "power_in"))
      (node (ref "MEGA1") (pin "6") (pinfunction "VCC_6") (pintype "power_in"))
      (node (ref "MEGA1-C1") (pin "1") (pinfunction "1_1") (pintype "passive"))
      (node (ref "MEGA2") (pin "18") (pinfunction "AVCC_18") (pintype "power_in"))
      (node (ref "MEGA2") (pin "20") (pinfunction "AREF_20") (pintype "passive"))
      (node (ref "MEGA2") (pin "4") (pinfunction "VCC_4") (pintype "power_in"))
      (node (ref "MEGA2") (pin "6") (pinfunction "VCC_6") (pintype "power_in"))
      (node (ref "MEGA2-C1") (pin "2") (pinfunction "2_2") (pintype "passive"))
      (node (ref "MOTORDRIVER") (pin "11") (pinfunction "11_11") (pintype "passive"))
      (node (ref "MPU") (pin "P$4") (pinfunction "4_P$4") (pintype "bidirectional"))
      (node (ref "R2") (pin "1") (pinfunction "1_1") (pintype "passive"))
      (node (ref "S2") (pin "1") (pinfunction "O_1") (pintype "passive"))
      (node (ref "SPI-R") (pin "P$1") (pinfunction "1_P$1") (pintype "bidirectional"))
      (node (ref "SRAM-R1") (pin "2") (pinfunction "2_2") (pintype "passive"))
      (node (ref "SRAM-R2") (pin "2") (pinfunction "2_2") (pintype "passive"))
      (node (ref "SS-R1") (pin "2") (pinfunction "2_2") (pintype "passive"))
      (node (ref "SS-R2") (pin "2") (pinfunction "2_2") (pintype "passive"))
      (node (ref "SUPPLY3.3V") (pin "1") (pinfunction "KL_1") (pintype "passive"))
      (node (ref "SV1") (pin "2") (pinfunction "2_2") (pintype "passive"))
      (node (ref "TO-UNDER") (pin "24") (pinfunction "24_24") (pintype "passive"))
      (node (ref "TOUCH1") (pin "P$2") (pinfunction "2_P$2") (pintype "bidirectional"))
      (node (ref "TOUCH2") (pin "P$2") (pinfunction "2_P$2") (pintype "bidirectional"))
      (node (ref "TW-SP") (pin "P$2") (pinfunction "2_P$2") (pintype "bidirectional"))
      (node (ref "U$2") (pin "4") (pinfunction "S_4") (pintype "passive"))
      (node (ref "U1") (pin "14") (pinfunction "VCC_14") (pintype "power_in"))
      (node (ref "U1") (pin "24") (pinfunction "VCC_24") (pintype "power_in"))
      (node (ref "U1") (pin "34") (pinfunction "VCC_34") (pintype "power_in"))
      (node (ref "U1") (pin "4") (pinfunction "AVCC_4") (pintype "power_in"))
      (node (ref "U1") (pin "44") (pinfunction "VCC_44") (pintype "power_in"))
      (node (ref "U1") (pin "54") (pinfunction "VCC_54") (pintype "power_in"))
      (node (ref "U1") (pin "64") (pinfunction "VCC_64") (pintype "power_in"))
      (node (ref "U1") (pin "74") (pinfunction "VCC_74") (pintype "power_in"))
      (node (ref "U1") (pin "83") (pinfunction "VCC_83") (pintype "power_in"))
      (node (ref "U1") (pin "94") (pinfunction "AVCC_94") (pintype "power_in"))
      (node (ref "U2") (pin "8") (pinfunction "VCC_8") (pintype "power_in"))
      (node (ref "X-R1") (pin "2") (pinfunction "2_2") (pintype "passive"))
      (node (ref "XMEGA-C1") (pin "1") (pinfunction "1_1") (pintype "passive"))
      (node (ref "XMEGA-C2") (pin "1") (pinfunction "1_1") (pintype "passive"))
      (node (ref "XMEGA-TEST1") (pin "1") (pinfunction "1_1") (pintype "passive"))
      (node (ref "XMEGA-TEST1") (pin "2") (pinfunction "2_2") (pintype "passive"))
      (node (ref "XMEGA-TEST2") (pin "1") (pinfunction "1_1") (pintype "passive"))
      (node (ref "XMEGA-TEST2") (pin "2") (pinfunction "2_2") (pintype "passive"))
      (node (ref "XMEGA-TEST3") (pin "1") (pinfunction "1_1") (pintype "passive"))
      (node (ref "XMEGA-TEST3") (pin "2") (pinfunction "2_2") (pintype "passive"))
    )
    (net (code "2") (name "+5V") (class "Default")
      (node (ref "5C1") (pin "+") (pinfunction "+_+") (pintype "passive"))
      (node (ref "5C2") (pin "1") (pinfunction "1_1") (pintype "passive"))
      (node (ref "5VREG") (pin "4") (pinfunction "VOUT_4") (pintype "bidirectional"))
      (node (ref "5VREG") (pin "5") (pinfunction "SENSE_5") (pintype "bidirectional"))
      (node (ref "C2") (pin "1") (pinfunction "1_1") (pintype "passive"))
      (node (ref "IC2") (pin "9") (pinfunction "CD+_9") (pintype "passive"))
      (node (ref "INDILED1") (pin "2") (pinfunction "2_2") (pintype "passive"))
      (node (ref "INDILED2") (pin "2") (pinfunction "2_2") (pintype "passive"))
      (node (ref "INDILED3") (pin "2") (pinfunction "2_2") (pintype "passive"))
      (node (ref "INDILED4") (pin "2") (pinfunction "2_2") (pintype "passive"))
      (node (ref "J1") (pin "P$1") (pinfunction "1_P$1") (pintype "bidirectional"))
      (node (ref "R1") (pin "1") (pinfunction "1_1") (pintype "passive"))
      (node (ref "S2") (pin "3") (pinfunction "S_3") (pintype "passive"))
      (node (ref "SP-LED") (pin "A") (pinfunction "A_A") (pintype "passive"))
      (node (ref "SUPPLY5V") (pin "1") (pinfunction "KL_1") (pintype "passive"))
      (node (ref "U$2") (pin "3") (pinfunction "S_3") (pintype "passive"))
    )
    (net (code "3") (name "+9V") (class "Default")
      (node (ref "3.3REG") (pin "2") (pinfunction "VIN_2") (pintype "bidirectional"))
      (node (ref "5VREG") (pin "2") (pinfunction "VIN_2") (pintype "bidirectional"))
      (node (ref "9C1") (pin "+") (pinfunction "+_+") (pintype "passive"))
      (node (ref "9C2") (pin "1") (pinfunction "1_1") (pintype "passive"))
      (node (ref "C1") (pin "1") (pinfunction "1_1") (pintype "passive"))
      (node (ref "C3") (pin "1") (pinfunction "1_1") (pintype "passive"))
      (node (ref "MAIN-SPL") (pin "P$1") (pinfunction "1_P$1") (pintype "bidirectional"))
      (node (ref "Q4") (pin "S") (pinfunction "S_S") (pintype "passive"))
      (node (ref "Q5") (pin "D") (pinfunction "D_D") (pintype "passive"))
      (node (ref "SP-R2") (pin "2") (pinfunction "2_2") (pintype "passive"))
      (node (ref "SP-R4") (pin "2") (pinfunction "2_2") (pintype "passive"))
      (node (ref "SP-R5") (pin "2") (pinfunction "2_2") (pintype "passive"))
      (node (ref "VOLTAGE-METER1") (pin "P$1") (pinfunction "1_P$1") (pintype "bidirectional"))
    )
    (net (code "4") (name "/CK") (class "Default")
      (node (ref "TO-UNDER") (pin "6") (pinfunction "6_6") (pintype "passive"))
      (node (ref "U1") (pin "46") (pinfunction "PF1_46") (pintype "bidirectional"))
    )
    (net (code "5") (name "/CS") (class "Default")
      (node (ref "SRAM-R1") (pin "1") (pinfunction "1_1") (pintype "passive"))
      (node (ref "U1") (pin "82") (pinfunction "PK7_82") (pintype "bidirectional"))
      (node (ref "U2") (pin "1") (pinfunction "~{CS}_1") (pintype "input"))
    )
    (net (code "6") (name "/DOUT") (class "Default")
      (node (ref "TO-UNDER") (pin "4") (pinfunction "4_4") (pintype "passive"))
      (node (ref "U1") (pin "48") (pinfunction "PF3_48") (pintype "bidirectional"))
    )
    (net (code "7") (name "/FT-RESET") (class "Default")
      (node (ref "IC1") (pin "6") (pinfunction "~{RI}_6") (pintype "input"))
      (node (ref "S1") (pin "15") (pinfunction "2_15") (pintype "passive"))
      (node (ref "S1") (pin "16") (pinfunction "2_16") (pintype "passive"))
    )
    (net (code "8") (name "/FT232-RXD") (class "Default")
      (node (ref "IC1") (pin "5") (pinfunction "RXD_5") (pintype "input"))
      (node (ref "L5") (pin "A") (pinfunction "A_A") (pintype "passive"))
      (node (ref "S1") (pin "10") (pinfunction "2_10") (pintype "passive"))
      (node (ref "S1") (pin "12") (pinfunction "2_12") (pintype "passive"))
      (node (ref "S1") (pin "14") (pinfunction "2_14") (pintype "passive"))
      (node (ref "TWILITE") (pin "4") (pinfunction "4_4") (pintype "passive"))
    )
    (net (code "9") (name "/FT232-TXD") (class "Default")
      (node (ref "IC1") (pin "1") (pinfunction "TXD_1") (pintype "output"))
      (node (ref "L6") (pin "A") (pinfunction "A_A") (pintype "passive"))
      (node (ref "S1") (pin "11") (pinfunction "2_11") (pintype "passive"))
      (node (ref "S1") (pin "13") (pinfunction "2_13") (pintype "passive"))
      (node (ref "S1") (pin "9") (pinfunction "2_9") (pintype "passive"))
      (node (ref "TWILITE") (pin "2") (pinfunction "2_2") (pintype "passive"))
    )
    (net (code "10") (name "/GATE") (class "Default")
      (node (ref "TO-UNDER") (pin "5") (pinfunction "5_5") (pintype "passive"))
      (node (ref "U1") (pin "47") (pinfunction "PF2_47") (pintype "bidirectional"))
    )
    (net (code "11") (name "/HOLD") (class "Default")
      (node (ref "SRAM-R2") (pin "1") (pinfunction "1_1") (pintype "passive"))
      (node (ref "U2") (pin "7") (pinfunction "~{HOLD}_7") (pintype "input"))
    )
    (net (code "12") (name "/M1CS") (class "Default")
      (node (ref "MEGA1") (pin "25") (pinfunction "PC2(ADC2)_25") (pintype "bidirectional"))
      (node (ref "MOTORDRIVER") (pin "6") (pinfunction "6_6") (pintype "passive"))
    )
    (net (code "13") (name "/M1EN") (class "Default")
      (node (ref "MEGA1") (pin "28") (pinfunction "PC5(ADC5/SCL)_28") (pintype "bidirectional"))
      (node (ref "MOTORDRIVER") (pin "10") (pinfunction "10_10") (pintype "passive"))
    )
    (net (code "14") (name "/M1INA") (class "Default")
      (node (ref "MEGA1") (pin "27") (pinfunction "PC4(ADC4/SDA)_27") (pintype "bidirectional"))
      (node (ref "MOTORDRIVER") (pin "9") (pinfunction "9_9") (pintype "passive"))
    )
    (net (code "15") (name "/M1INB") (class "Default")
      (node (ref "MEGA1") (pin "26") (pinfunction "PC3(ADC3)_26") (pintype "bidirectional"))
      (node (ref "MOTORDRIVER") (pin "8") (pinfunction "8_8") (pintype "passive"))
    )
    (net (code "16") (name "/M1PWM") (class "Default")
      (node (ref "MEGA1") (pin "10") (pinfunction "PD6(AIN0)_10") (pintype "bidirectional"))
      (node (ref "MOTORDRIVER") (pin "7") (pinfunction "7_7") (pintype "passive"))
    )
    (net (code "17") (name "/M2CS") (class "Default")
      (node (ref "MEGA2") (pin "25") (pinfunction "PC2(ADC2)_25") (pintype "bidirectional"))
      (node (ref "MOTORDRIVER") (pin "1") (pinfunction "1_1") (pintype "passive"))
    )
    (net (code "18") (name "/M2EN") (class "Default")
      (node (ref "MEGA2") (pin "28") (pinfunction "PC5(ADC5/SCL)_28") (pintype "bidirectional"))
      (node (ref "MOTORDRIVER") (pin "5") (pinfunction "5_5") (pintype "passive"))
    )
    (net (code "19") (name "/M2INA") (class "Default")
      (node (ref "MEGA2") (pin "27") (pinfunction "PC4(ADC4/SDA)_27") (pintype "bidirectional"))
      (node (ref "MOTORDRIVER") (pin "4") (pinfunction "4_4") (pintype "passive"))
    )
    (net (code "20") (name "/M2INB") (class "Default")
      (node (ref "MEGA2") (pin "26") (pinfunction "PC3(ADC3)_26") (pintype "bidirectional"))
      (node (ref "MOTORDRIVER") (pin "3") (pinfunction "3_3") (pintype "passive"))
    )
    (net (code "21") (name "/M2PWM") (class "Default")
      (node (ref "MEGA2") (pin "10") (pinfunction "PD6(AIN0)_10") (pintype "bidirectional"))
      (node (ref "MOTORDRIVER") (pin "2") (pinfunction "2_2") (pintype "passive"))
    )
    (net (code "22") (name "/MISO-M") (class "Default")
      (node (ref "IC1") (pin "11") (pinfunction "~{CTS}_11") (pintype "input"))
      (node (ref "MEGA1") (pin "16") (pinfunction "PB4(MISO)_16") (pintype "bidirectional"))
      (node (ref "MEGA2") (pin "16") (pinfunction "PB4(MISO)_16") (pintype "bidirectional"))
      (node (ref "SPI-SW") (pin "2") (pinfunction "2_2") (pintype "passive"))
    )
    (net (code "23") (name "/MISO-X") (class "Default")
      (node (ref "SPI-SW") (pin "5") (pinfunction "5_5") (pintype "passive"))
      (node (ref "U1") (pin "21") (pinfunction "PC6_21") (pintype "bidirectional"))
    )
    (net (code "24") (name "/MISOD") (class "Default")
      (node (ref "TO-UNDER") (pin "15") (pinfunction "15_15") (pintype "passive"))
      (node (ref "U1") (pin "31") (pinfunction "PD6_31") (pintype "bidirectional"))
    )
    (net (code "25") (name "/MISOF") (class "Default")
      (node (ref "SPI-R") (pin "P$4") (pinfunction "4_P$4") (pintype "bidirectional"))
      (node (ref "U1") (pin "51") (pinfunction "PF6_51") (pintype "bidirectional"))
      (node (ref "U2") (pin "2") (pinfunction "SO_2") (pintype "output"))
    )
    (net (code "26") (name "/MOSI-M") (class "Default")
      (node (ref "IC1") (pin "10") (pinfunction "~{DCD}_10") (pintype "input"))
      (node (ref "MEGA1") (pin "15") (pinfunction "PB3(MOSI/OC2)_15") (pintype "bidirectional"))
      (node (ref "MEGA2") (pin "15") (pinfunction "PB3(MOSI/OC2)_15") (pintype "bidirectional"))
      (node (ref "SPI-SW") (pin "3") (pinfunction "3_3") (pintype "passive"))
    )
    (net (code "27") (name "/MOSI-X") (class "Default")
      (node (ref "SPI-SW") (pin "4") (pinfunction "4_4") (pintype "passive"))
      (node (ref "U1") (pin "20") (pinfunction "PC5_20") (pintype "bidirectional"))
    )
    (net (code "28") (name "/MOSID") (class "Default")
      (node (ref "TO-UNDER") (pin "16") (pinfunction "16_16") (pintype "passive"))
      (node (ref "U1") (pin "30") (pinfunction "PD5_30") (pintype "bidirectional"))
    )
    (net (code "29") (name "/MOSIF") (class "Default")
      (node (ref "SPI-R") (pin "P$3") (pinfunction "3_P$3") (pintype "bidirectional"))
      (node (ref "U1") (pin "50") (pinfunction "PF5_50") (pintype "bidirectional"))
      (node (ref "U2") (pin "5") (pinfunction "SI_5") (pintype "input"))
    )
    (net (code "30") (name "/MV1") (class "Default")
      (node (ref "TO-UNDER") (pin "19") (pinfunction "19_19") (pintype "passive"))
      (node (ref "U1") (pin "27") (pinfunction "PD2_27") (pintype "bidirectional"))
    )
    (net (code "31") (name "/MV2") (class "Default")
      (node (ref "TO-UNDER") (pin "18") (pinfunction "18_18") (pintype "passive"))
      (node (ref "U1") (pin "28") (pinfunction "PD3_28") (pintype "bidirectional"))
    )
    (net (code "32") (name "/MV3") (class "Default")
      (node (ref "TO-UNDER") (pin "17") (pinfunction "17_17") (pintype "passive"))
      (node (ref "U1") (pin "29") (pinfunction "PD4_29") (pintype "bidirectional"))
    )
    (net (code "33") (name "/MVS1") (class "Default")
      (node (ref "TO-UNDER") (pin "1") (pinfunction "1_1") (pintype "passive"))
      (node (ref "U1") (pin "70") (pinfunction "PJ5_70") (pintype "bidirectional"))
    )
    (net (code "34") (name "/MVS2") (class "Default")
      (node (ref "TO-UNDER") (pin "2") (pinfunction "2_2") (pintype "passive"))
      (node (ref "U1") (pin "71") (pinfunction "PJ6_71") (pintype "bidirectional"))
    )
    (net (code "35") (name "/MVS3") (class "Default")
      (node (ref "TO-UNDER") (pin "3") (pinfunction "3_3") (pintype "passive"))
      (node (ref "U1") (pin "72") (pinfunction "PJ7_72") (pintype "bidirectional"))
    )
    (net (code "36") (name "/PA0") (class "Default")
      (node (ref "SG1") (pin "1") (pinfunction "1_1") (pintype "passive"))
      (node (ref "U1") (pin "95") (pinfunction "PA0_95") (pintype "bidirectional"))
      (node (ref "X-R2") (pin "2") (pinfunction "2_2") (pintype "passive"))
    )
    (net (code "37") (name "/PH0") (class "Default")
      (node (ref "TESTSW-R1") (pin "2") (pinfunction "2_2") (pintype "passive"))
      (node (ref "U1") (pin "55") (pinfunction "PH0_55") (pintype "bidirectional"))
      (node (ref "XMEGA-TEST1") (pin "3") (pinfunction "3_3") (pintype "passive"))
      (node (ref "XMEGA-TEST1") (pin "4") (pinfunction "4_4") (pintype "passive"))
    )
    (net (code "38") (name "/PH1") (class "Default")
      (node (ref "TESTSW-R2") (pin "2") (pinfunction "2_2") (pintype "passive"))
      (node (ref "U1") (pin "56") (pinfunction "PH1_56") (pintype "bidirectional"))
      (node (ref "XMEGA-TEST2") (pin "3") (pinfunction "3_3") (pintype "passive"))
      (node (ref "XMEGA-TEST2") (pin "4") (pinfunction "4_4") (pintype "passive"))
    )
    (net (code "39") (name "/PH2") (class "Default")
      (node (ref "TESTSW-R3") (pin "2") (pinfunction "2_2") (pintype "passive"))
      (node (ref "U1") (pin "57") (pinfunction "PH2_57") (pintype "bidirectional"))
      (node (ref "XMEGA-TEST3") (pin "3") (pinfunction "3_3") (pintype "passive"))
      (node (ref "XMEGA-TEST3") (pin "4") (pinfunction "4_4") (pintype "passive"))
    )
    (net (code "40") (name "/PING1") (class "Default")
      (node (ref "TO-UNDER") (pin "13") (pinfunction "13_13") (pintype "passive"))
      (node (ref "U1") (pin "35") (pinfunction "PE0_35") (pintype "bidirectional"))
    )
    (net (code "41") (name "/PING2") (class "Default")
      (node (ref "TO-UNDER") (pin "12") (pinfunction "12_12") (pintype "passive"))
      (node (ref "U1") (pin "36") (pinfunction "PE1_36") (pintype "bidirectional"))
    )
    (net (code "42") (name "/PING3") (class "Default")
      (node (ref "TO-UNDER") (pin "11") (pinfunction "11_11") (pintype "passive"))
      (node (ref "U1") (pin "37") (pinfunction "PE2_37") (pintype "bidirectional"))
    )
    (net (code "43") (name "/PING4") (class "Default")
      (node (ref "TO-UNDER") (pin "10") (pinfunction "10_10") (pintype "passive"))
      (node (ref "U1") (pin "38") (pinfunction "PE3_38") (pintype "bidirectional"))
    )
    (net (code "44") (name "/PING5") (class "Default")
      (node (ref "TO-UNDER") (pin "9") (pinfunction "9_9") (pintype "passive"))
      (node (ref "U1") (pin "39") (pinfunction "PE4_39") (pintype "bidirectional"))
    )
    (net (code "45") (name "/PING6") (class "Default")
      (node (ref "TO-UNDER") (pin "8") (pinfunction "8_8") (pintype "passive"))
      (node (ref "U1") (pin "40") (pinfunction "PE5_40") (pintype "bidirectional"))
    )
    (net (code "46") (name "/PJ0") (class "Default")
      (node (ref "TOUCH1") (pin "P$1") (pinfunction "1_P$1") (pintype "bidirectional"))
      (node (ref "U1") (pin "65") (pinfunction "PJ0_65") (pintype "bidirectional"))
    )
    (net (code "47") (name "/PJ1") (class "Default")
      (node (ref "TOUCH2") (pin "P$1") (pinfunction "1_P$1") (pintype "bidirectional"))
      (node (ref "U1") (pin "66") (pinfunction "PJ1_66") (pintype "bidirectional"))
    )
    (net (code "48") (name "/PK4") (class "Default")
      (node (ref "L3") (pin "A") (pinfunction "A_A") (pintype "passive"))
      (node (ref "U1") (pin "79") (pinfunction "PK4_79") (pintype "bidirectional"))
    )
    (net (code "49") (name "/PK5") (class "Default")
      (node (ref "L4") (pin "A") (pinfunction "A_A") (pintype "passive"))
      (node (ref "U1") (pin "80") (pinfunction "PK5_80") (pintype "bidirectional"))
    )
    (net (code "50") (name "/PQ0") (class "Default")
      (node (ref "R-R") (pin "1") (pinfunction "1_1") (pintype "passive"))
      (node (ref "U1") (pin "85") (pinfunction "PQ0_85") (pintype "bidirectional"))
    )
    (net (code "51") (name "/PQ1") (class "Default")
      (node (ref "R-G") (pin "1") (pinfunction "1_1") (pintype "passive"))
      (node (ref "U1") (pin "86") (pinfunction "PQ1_86") (pintype "bidirectional"))
    )
    (net (code "52") (name "/PQ2") (class "Default")
      (node (ref "R-B") (pin "1") (pinfunction "1_1") (pintype "passive"))
      (node (ref "U1") (pin "87") (pinfunction "PQ2_87") (pintype "bidirectional"))
    )
    (net (code "53") (name "/RANGE") (class "Default")
      (node (ref "TO-UNDER") (pin "7") (pinfunction "7_7") (pintype "passive"))
      (node (ref "U1") (pin "45") (pinfunction "PF0_45") (pintype "bidirectional"))
    )
    (net (code "54") (name "/RESET-M1") (class "Default")
      (node (ref "M1-R1") (pin "1") (pinfunction "1_1") (pintype "passive"))
      (node (ref "MEGA1") (pin "29") (pinfunction "PC6(/RESET)_29") (pintype "bidirectional"))
      (node (ref "RESET-MEGA1") (pin "1") (pinfunction "1_1") (pintype "passive"))
      (node (ref "RESET-MEGA1") (pin "2") (pinfunction "2_2") (pintype "passive"))
      (node (ref "S1") (pin "1") (pinfunction "1_1") (pintype "passive"))
    )
    (net (code "55") (name "/RESET-M2") (class "Default")
      (node (ref "M2-R1") (pin "1") (pinfunction "1_1") (pintype "passive"))
      (node (ref "MEGA2") (pin "29") (pinfunction "PC6(/RESET)_29") (pintype "bidirectional"))
      (node (ref "RESET-MEGA2") (pin "1") (pinfunction "1_1") (pintype "passive"))
      (node (ref "RESET-MEGA2") (pin "2") (pinfunction "2_2") (pintype "passive"))
      (node (ref "S1") (pin "2") (pinfunction "1_2") (pintype "passive"))
    )
    (net (code "56") (name "/RO1") (class "Default")
      (node (ref "MEGA1") (pin "32") (pinfunction "PD2(INT0)_32") (pintype "bidirectional"))
      (node (ref "TO-UNDER") (pin "25") (pinfunction "25_25") (pintype "passive"))
    )
    (net (code "57") (name "/RO2") (class "Default")
      (node (ref "MEGA2") (pin "32") (pinfunction "PD2(INT0)_32") (pintype "bidirectional"))
      (node (ref "TO-UNDER") (pin "26") (pinfunction "26_26") (pintype "passive"))
    )
    (net (code "58") (name "/RXDM1") (class "Default")
      (node (ref "MEGA1") (pin "30") (pinfunction "PD0(RXD)_30") (pintype "bidirectional"))
      (node (ref "S1") (pin "6") (pinfunction "1_6") (pintype "passive"))
    )
    (net (code "59") (name "/RXDM2") (class "Default")
      (node (ref "MEGA2") (pin "30") (pinfunction "PD0(RXD)_30") (pintype "bidirectional"))
      (node (ref "S1") (pin "4") (pinfunction "1_4") (pintype "passive"))
    )
    (net (code "60") (name "/RXDX1") (class "Default")
      (node (ref "S1") (pin "8") (pinfunction "1_8") (pintype "passive"))
      (node (ref "U1") (pin "17") (pinfunction "PC2_17") (pintype "bidirectional"))
    )
    (net (code "61") (name "/SCK-M") (class "Default")
      (node (ref "IC1") (pin "9") (pinfunction "~{DSR}_9") (pintype "input"))
      (node (ref "MEGA1") (pin "17") (pinfunction "PB5(SCK)_17") (pintype "bidirectional"))
      (node (ref "MEGA2") (pin "17") (pinfunction "PB5(SCK)_17") (pintype "bidirectional"))
      (node (ref "SPI-SW") (pin "1") (pinfunction "1_1") (pintype "passive"))
    )
    (net (code "62") (name "/SCK-X") (class "Default")
      (node (ref "SPI-SW") (pin "6") (pinfunction "6_6") (pintype "passive"))
      (node (ref "U1") (pin "22") (pinfunction "PC7_22") (pintype "bidirectional"))
    )
    (net (code "63") (name "/SCKD") (class "Default")
      (node (ref "TO-UNDER") (pin "14") (pinfunction "14_14") (pintype "passive"))
      (node (ref "U1") (pin "32") (pinfunction "PD7_32") (pintype "bidirectional"))
    )
    (net (code "64") (name "/SCKF") (class "Default")
      (node (ref "SPI-R") (pin "P$2") (pinfunction "2_P$2") (pintype "bidirectional"))
      (node (ref "U1") (pin "52") (pinfunction "PF7_52") (pintype "bidirectional"))
      (node (ref "U2") (pin "6") (pinfunction "SCK_6") (pintype "input"))
    )
    (net (code "65") (name "/SCL-C") (class "Default")
      (node (ref "I2C-R") (pin "P$1") (pinfunction "1_P$1") (pintype "bidirectional"))
      (node (ref "MPU") (pin "P$2") (pinfunction "2_P$2") (pintype "bidirectional"))
      (node (ref "U1") (pin "16") (pinfunction "PC1_16") (pintype "bidirectional"))
    )
    (net (code "66") (name "/SCL-D") (class "Default")
      (node (ref "LCD") (pin "3") (pinfunction "3_3") (pintype "passive"))
      (node (ref "TO-UNDER") (pin "20") (pinfunction "20_20") (pintype "passive"))
      (node (ref "U1") (pin "26") (pinfunction "PD1_26") (pintype "bidirectional"))
    )
    (net (code "67") (name "/SDA-C") (class "Default")
      (node (ref "I2C-R") (pin "P$2") (pinfunction "2_P$2") (pintype "bidirectional"))
      (node (ref "MPU") (pin "P$3") (pinfunction "3_P$3") (pintype "bidirectional"))
      (node (ref "U1") (pin "15") (pinfunction "PC0_15") (pintype "bidirectional"))
    )
    (net (code "68") (name "/SDA-D") (class "Default")
      (node (ref "LCD") (pin "4") (pinfunction "4_4") (pintype "passive"))
      (node (ref "TO-UNDER") (pin "21") (pinfunction "21_21") (pintype "passive"))
      (node (ref "U1") (pin "25") (pinfunction "PD0_25") (pintype "bidirectional"))
    )
    (net (code "69") (name "/SIG1") (class "Default")
      (node (ref "MEGA1") (pin "1") (pinfunction "PD3(INT1)_1") (pintype "bidirectional"))
      (node (ref "U1") (pin "5") (pinfunction "PB0_5") (pintype "bidirectional"))
    )
    (net (code "70") (name "/SIG2") (class "Default")
      (node (ref "MEGA2") (pin "1") (pinfunction "PD3(INT1)_1") (pintype "bidirectional"))
      (node (ref "U1") (pin "6") (pinfunction "PB1_6") (pintype "bidirectional"))
    )
    (net (code "71") (name "/SS-R") (class "Default")
      (node (ref "SPI-R") (pin "P$5") (pinfunction "5_P$5") (pintype "bidirectional"))
      (node (ref "U1") (pin "49") (pinfunction "PF4_49") (pintype "bidirectional"))
    )
    (net (code "72") (name "/SS1") (class "Default")
      (node (ref "MEGA1") (pin "14") (pinfunction "PB2(SS/OC1B)_14") (pintype "bidirectional"))
      (node (ref "SS-R1") (pin "1") (pinfunction "1_1") (pintype "passive"))
      (node (ref "U1") (pin "7") (pinfunction "PB2_7") (pintype "bidirectional"))
    )
    (net (code "73") (name "/SS2") (class "Default")
      (node (ref "MEGA2") (pin "14") (pinfunction "PB2(SS/OC1B)_14") (pintype "bidirectional"))
      (node (ref "SS-R2") (pin "1") (pinfunction "1_1") (pintype "passive"))
      (node (ref "U1") (pin "8") (pinfunction "PB3_8") (pintype "bidirectional"))
    )
    (net (code "74") (name "/TCK") (class "Default")
      (node (ref "JTAG") (pin "1") (pinfunction "1_1") (pintype "passive"))
      (node (ref "U1") (pin "11") (pinfunction "PB6_11") (pintype "bidirectional"))
    )
    (net (code "75") (name "/TDI") (class "Default")
      (node (ref "JTAG") (pin "9") (pinfunction "9_9") (pintype "passive"))
      (node (ref "U1") (pin "10") (pinfunction "PB5_10") (pintype "bidirectional"))
    )
    (net (code "76") (name "/TDO") (class "Default")
      (node (ref "JTAG") (pin "3") (pinfunction "3_3") (pintype "passive"))
      (node (ref "U1") (pin "12") (pinfunction "PB7_12") (pintype "bidirectional"))
    )
    (net (code "77") (name "/TMS") (class "Default")
      (node (ref "JTAG") (pin "5") (pinfunction "5_5") (pintype "passive"))
      (node (ref "U1") (pin "9") (pinfunction "PB4_9") (pintype "bidirectional"))
    )
    (net (code "78") (name "/TXDM1") (class "Default")
      (node (ref "MEGA1") (pin "31") (pinfunction "PD1(TXD)_31") (pintype "bidirectional"))
      (node (ref "S1") (pin "5") (pinfunction "1_5") (pintype "passive"))
    )
    (net (code "79") (name "/TXDM2") (class "Default")
      (node (ref "MEGA2") (pin "31") (pinfunction "PD1(TXD)_31") (pintype "bidirectional"))
      (node (ref "S1") (pin "3") (pinfunction "1_3") (pintype "passive"))
    )
    (net (code "80") (name "/TXDX1") (class "Default")
      (node (ref "S1") (pin "7") (pinfunction "1_7") (pintype "passive"))
      (node (ref "U1") (pin "18") (pinfunction "PC3_18") (pintype "bidirectional"))
    )
    (net (code "81") (name "/X-RESET") (class "Default")
      (node (ref "JTAG") (pin "6") (pinfunction "6_6") (pintype "passive"))
      (node (ref "LCD") (pin "2") (pinfunction "2_2") (pintype "passive"))
      (node (ref "RESET-XMEGA") (pin "1") (pinfunction "1_1") (pintype "passive"))
      (node (ref "RESET-XMEGA") (pin "2") (pinfunction "2_2") (pintype "passive"))
      (node (ref "SV1") (pin "5") (pinfunction "5_5") (pintype "passive"))
      (node (ref "U1") (pin "90") (pinfunction "~{RESET}/PDI_90") (pintype "bidirectional"))
      (node (ref "X-R1") (pin "1") (pinfunction "1_1") (pintype "passive"))
    )
    (net (code "82") (name "GND") (class "Default")
      (node (ref "3.3C1") (pin "-") (pinfunction "-_-") (pintype "passive"))
      (node (ref "3.3C2") (pin "2") (pinfunction "2_2") (pintype "passive"))
      (node (ref "3.3REG") (pin "3") (pinfunction "GND_1_3") (pintype "bidirectional"))
      (node (ref "3.3REG") (pin "7") (pinfunction "GND_2_7") (pintype "bidirectional"))
      (node (ref "5C1") (pin "-") (pinfunction "-_-") (pintype "passive"))
      (node (ref "5C2") (pin "2") (pinfunction "2_2") (pintype "passive"))
      (node (ref "5VREG") (pin "3") (pinfunction "GND_1_3") (pintype "bidirectional"))
      (node (ref "5VREG") (pin "7") (pinfunction "GND_2_7") (pintype "bidirectional"))
      (node (ref "9C1") (pin "-") (pinfunction "-_-") (pintype "passive"))
      (node (ref "9C2") (pin "2") (pinfunction "2_2") (pintype "passive"))
      (node (ref "C1") (pin "2") (pinfunction "2_2") (pintype "passive"))
      (node (ref "C2") (pin "2") (pinfunction "2_2") (pintype "passive"))
      (node (ref "C3") (pin "2") (pinfunction "2_2") (pintype "passive"))
      (node (ref "C4") (pin "2") (pinfunction "2_2") (pintype "passive"))
      (node (ref "ERROR1-R") (pin "1") (pinfunction "1_1") (pintype "passive"))
      (node (ref "ERROR2-R") (pin "1") (pinfunction "1_1") (pintype "passive"))
      (node (ref "FT232-R11") (pin "1") (pinfunction "1_1") (pintype "passive"))
      (node (ref "FT232-R12") (pin "1") (pinfunction "1_1") (pintype "passive"))
      (node (ref "FT232-R8") (pin "1") (pinfunction "1_1") (pintype "passive"))
      (node (ref "FT232-R9") (pin "1") (pinfunction "1_1") (pintype "passive"))
      (node (ref "FT232USBCON") (pin "5") (pinfunction "5_5") (pintype "passive"))
      (node (ref "FT232USBCON") (pin "M1") (pinfunction "S1_M1") (pintype "passive"))
      (node (ref "FT232USBCON") (pin "M2") (pinfunction "S2_M2") (pintype "passive"))
      (node (ref "FT232USBCON") (pin "M3") (pinfunction "S3_M3") (pintype "passive"))
      (node (ref "FT232USBCON") (pin "M4") (pinfunction "S4_M4") (pintype "passive"))
      (node (ref "GND-CH") (pin "1") (pinfunction "P_1") (pintype "passive"))
      (node (ref "GND-CHK") (pin "1") (pinfunction "P_1") (pintype "passive"))
      (node (ref "GND-CHK1") (pin "1") (pinfunction "P_1") (pintype "passive"))
      (node (ref "I2C-R") (pin "P$4") (pinfunction "4_P$4") (pintype "bidirectional"))
      (node (ref "IC1") (pin "18") (pinfunction "GND_18") (pintype "power_in"))
      (node (ref "IC1") (pin "21") (pinfunction "GND_21") (pintype "power_in"))
      (node (ref "IC1") (pin "25") (pinfunction "GND_25") (pintype "power_in"))
      (node (ref "IC1") (pin "26") (pinfunction "TEST_26") (pintype "input"))
      (node (ref "IC1") (pin "7") (pinfunction "GND_7") (pintype "power_in"))
      (node (ref "IC2") (pin "5") (pinfunction "I5_5") (pintype "input"))
      (node (ref "IC2") (pin "6") (pinfunction "I6_6") (pintype "input"))
      (node (ref "IC2") (pin "7") (pinfunction "I7_7") (pintype "input"))
      (node (ref "IC2") (pin "8") (pinfunction "GND_8") (pintype "power_in"))
      (node (ref "JTAG") (pin "10") (pinfunction "10_10") (pintype "passive"))
      (node (ref "JTAG") (pin "2") (pinfunction "2_2") (pintype "passive"))
      (node (ref "LCD") (pin "5") (pinfunction "5_5") (pintype "passive"))
      (node (ref "M-SW") (pin "3") (pinfunction "S_3") (pintype "passive"))
      (node (ref "MAIN-SPL") (pin "P$2") (pinfunction "2_P$2") (pintype "bidirectional"))
      (node (ref "MAINSW2") (pin "2") (pinfunction "2_2") (pintype "passive"))
      (node (ref "MEGA1") (pin "21") (pinfunction "GND_21") (pintype "power_in"))
      (node (ref "MEGA1") (pin "3") (pinfunction "GND_3") (pintype "power_in"))
      (node (ref "MEGA1") (pin "5") (pinfunction "GND_5") (pintype "power_in"))
      (node (ref "MEGA1-C1") (pin "2") (pinfunction "2_2") (pintype "passive"))
      (node (ref "MEGA2") (pin "21") (pinfunction "GND_21") (pintype "power_in"))
      (node (ref "MEGA2") (pin "3") (pinfunction "GND_3") (pintype "power_in"))
      (node (ref "MEGA2") (pin "5") (pinfunction "GND_5") (pintype "power_in"))
      (node (ref "MEGA2-C1") (pin "1") (pinfunction "1_1") (pintype "passive"))
      (node (ref "MOTORDRIVER") (pin "13") (pinfunction "13_13") (pintype "passive"))
      (node (ref "MPU") (pin "P$1") (pinfunction "1_P$1") (pintype "bidirectional"))
      (node (ref "Q1") (pin "2") (pinfunction "VSS_2") (pintype "power_in"))
      (node (ref "Q2") (pin "2") (pinfunction "VSS_2") (pintype "power_in"))
      (node (ref "Q3") (pin "G") (pinfunction "G_G") (pintype "passive"))
      (node (ref "R1") (pin "2") (pinfunction "2_2") (pintype "passive"))
      (node (ref "R2") (pin "2") (pinfunction "2_2") (pintype "passive"))
      (node (ref "RESET-MEGA1") (pin "3") (pinfunction "3_3") (pintype "passive"))
      (node (ref "RESET-MEGA1") (pin "4") (pinfunction "4_4") (pintype "passive"))
      (node (ref "RESET-MEGA2") (pin "3") (pinfunction "3_3") (pintype "passive"))
      (node (ref "RESET-MEGA2") (pin "4") (pinfunction "4_4") (pintype "passive"))
      (node (ref "RESET-XMEGA") (pin "3") (pinfunction "3_3") (pintype "passive"))
      (node (ref "RESET-XMEGA") (pin "4") (pinfunction "4_4") (pintype "passive"))
      (node (ref "SG1") (pin "2") (pinfunction "2_2") (pintype "passive"))
      (node (ref "SL-R1") (pin "1") (pinfunction "1_1") (pintype "passive"))
      (node (ref "SP-R1") (pin "1") (pinfunction "1_1") (pintype "passive"))
      (node (ref "SP-R3") (pin "1") (pinfunction "1_1") (pintype "passive"))
      (node (ref "SP-SW2") (pin "3") (pinfunction "3_3") (pintype "passive"))
      (node (ref "SP-SW2") (pin "4") (pinfunction "4_4") (pintype "passive"))
      (node (ref "SPI-R") (pin "P$6") (pinfunction "6_P$6") (pintype "bidirectional"))
      (node (ref "SUOPPLY-SW2") (pin "P$2") (pinfunction "2_P$2") (pintype "bidirectional"))
      (node (ref "SUPPLY3.3V") (pin "2") (pinfunction "KL_2") (pintype "passive"))
      (node (ref "SUPPLY5V") (pin "2") (pinfunction "KL_2") (pintype "passive"))
      (node (ref "SUPPLY9") (pin "2") (pinfunction "KL_2") (pintype "passive"))
      (node (ref "SV1") (pin "6") (pinfunction "6_6") (pintype "passive"))
      (node (ref "TESTSW-R1") (pin "1") (pinfunction "1_1") (pintype "passive"))
      (node (ref "TESTSW-R2") (pin "1") (pinfunction "1_1") (pintype "passive"))
      (node (ref "TESTSW-R3") (pin "1") (pinfunction "1_1") (pintype "passive"))
      (node (ref "TOUCH1") (pin "P$3") (pinfunction "3_P$3") (pintype "bidirectional"))
      (node (ref "TOUCH2") (pin "P$3") (pinfunction "3_P$3") (pintype "bidirectional"))
      (node (ref "TW-SP") (pin "P$1") (pinfunction "1_P$1") (pintype "bidirectional"))
      (node (ref "U$2") (pin "2") (pinfunction "S_2") (pintype "passive"))
      (node (ref "U1") (pin "13") (pinfunction "GND_13") (pintype "power_in"))
      (node (ref "U1") (pin "23") (pinfunction "GND_23") (pintype "power_in"))
      (node (ref "U1") (pin "3") (pinfunction "GND_3") (pintype "power_in"))
      (node (ref "U1") (pin "33") (pinfunction "GND_33") (pintype "power_in"))
      (node (ref "U1") (pin "43") (pinfunction "GND_43") (pintype "power_in"))
      (node (ref "U1") (pin "53") (pinfunction "GND_53") (pintype "power_in"))
      (node (ref "U1") (pin "63") (pinfunction "GND_63") (pintype "power_in"))
      (node (ref "U1") (pin "73") (pinfunction "GND_73") (pintype "power_in"))
      (node (ref "U1") (pin "84") (pinfunction "GND_84") (pintype "power_in"))
      (node (ref "U1") (pin "93") (pinfunction "GND_93") (pintype "power_in"))
      (node (ref "U2") (pin "4") (pinfunction "VSS_4") (pintype "power_in"))
      (node (ref "VOLTAGE-METER1") (pin "P$2") (pinfunction "2_P$2") (pintype "bidirectional"))
      (node (ref "VOLTAGE-METER2") (pin "P$2") (pinfunction "2_P$2") (pintype "bidirectional"))
      (node (ref "X-R2") (pin "1") (pinfunction "1_1") (pintype "passive"))
      (node (ref "X2") (pin "2") (pinfunction "2_2") (pintype "passive"))
      (node (ref "XMEGA-C1") (pin "2") (pinfunction "2_2") (pintype "passive"))
      (node (ref "XMEGA-C2") (pin "2") (pinfunction "2_2") (pintype "passive"))
    )
    (net (code "83") (name "Net-(3.3REG-ON{slash}OFF)") (class "Default")
      (node (ref "3.3REG") (pin "1") (pinfunction "ON/OFF_1") (pintype "bidirectional"))
      (node (ref "SP-R4") (pin "1") (pinfunction "1_1") (pintype "passive"))
      (node (ref "SP-SW2") (pin "2") (pinfunction "2_2") (pintype "passive"))
    )
    (net (code "84") (name "Net-(3.3REG-TRIM)") (class "Default")
      (node (ref "3.3REG") (pin "6") (pinfunction "TRIM_6") (pintype "bidirectional"))
      (node (ref "SP-RC2") (pin "3") (pinfunction "E_3") (pintype "passive"))
    )
    (net (code "85") (name "Net-(5VREG-ON{slash}OFF)") (class "Default")
      (node (ref "5VREG") (pin "1") (pinfunction "ON/OFF_1") (pintype "bidirectional"))
      (node (ref "SP-R2") (pin "1") (pinfunction "1_1") (pintype "passive"))
      (node (ref "SP-SW2") (pin "1") (pinfunction "1_1") (pintype "passive"))
    )
    (net (code "86") (name "Net-(5VREG-TRIM)") (class "Default")
      (node (ref "5VREG") (pin "6") (pinfunction "TRIM_6") (pintype "bidirectional"))
      (node (ref "SP-RC1") (pin "3") (pinfunction "E_3") (pintype "passive"))
    )
    (net (code "87") (name "Net-(CHECKLED-PadBLUE)") (class "Default")
      (node (ref "CHECKLED") (pin "BLUE") (pinfunction "BLUE_BLUE") (pintype "bidirectional"))
      (node (ref "R-B") (pin "2") (pinfunction "2_2") (pintype "passive"))
    )
    (net (code "88") (name "Net-(CHECKLED-PadGREEN)") (class "Default")
      (node (ref "CHECKLED") (pin "GREEN") (pinfunction "GREEN_GREEN") (pintype "bidirectional"))
      (node (ref "R-G") (pin "2") (pinfunction "2_2") (pintype "passive"))
    )
    (net (code "89") (name "Net-(CHECKLED-PadRED)") (class "Default")
      (node (ref "CHECKLED") (pin "RED") (pinfunction "RED_RED") (pintype "bidirectional"))
      (node (ref "R-R") (pin "2") (pinfunction "2_2") (pintype "passive"))
    )
    (net (code "90") (name "Net-(FT-POWERLED-PadC)") (class "Default")
      (node (ref "FT-POWERLED") (pin "C") (pinfunction "C_C") (pintype "passive"))
      (node (ref "FT232-R12") (pin "2") (pinfunction "2_2") (pintype "passive"))
    )
    (net (code "91") (name "Net-(FT232-R8-Pad2)") (class "Default")
      (node (ref "FT232-R8") (pin "2") (pinfunction "2_2") (pintype "passive"))
      (node (ref "L6") (pin "C") (pinfunction "C_C") (pintype "passive"))
    )
    (net (code "92") (name "Net-(FT232-R9-Pad2)") (class "Default")
      (node (ref "FT232-R9") (pin "2") (pinfunction "2_2") (pintype "passive"))
      (node (ref "L5") (pin "C") (pinfunction "C_C") (pintype "passive"))
    )
    (net (code "93") (name "Net-(FT232-R13-Pad2)") (class "Default")
      (node (ref "FT232-R13") (pin "2") (pinfunction "2_2") (pintype "passive"))
      (node (ref "FT232USBCON") (pin "3") (pinfunction "3_3") (pintype "passive"))
    )
    (net (code "94") (name "Net-(FT232-R14-Pad2)") (class "Default")
      (node (ref "FT232-R14") (pin "2") (pinfunction "2_2") (pintype "passive"))
      (node (ref "FT232USBCON") (pin "2") (pinfunction "2_2") (pintype "passive"))
    )
    (net (code "95") (name "Net-(IC1-3V3OUT)") (class "Default")
      (node (ref "IC1") (pin "17") (pinfunction "3V3OUT_17") (pintype "output"))
      (node (ref "IC1") (pin "4") (pinfunction "VCCIO_4") (pintype "power_in"))
    )
    (net (code "96") (name "Net-(IC1-USBDM)") (class "Default")
      (node (ref "FT232-R14") (pin "1") (pinfunction "1_1") (pintype "passive"))
      (node (ref "IC1") (pin "16") (pinfunction "USBDM_16") (pintype "bidirectional"))
    )
    (net (code "97") (name "Net-(IC1-USBDP)") (class "Default")
      (node (ref "FT232-R13") (pin "1") (pinfunction "1_1") (pintype "passive"))
      (node (ref "IC1") (pin "15") (pinfunction "USBDP_15") (pintype "bidirectional"))
    )
    (net (code "98") (name "Net-(IC1-VCC)") (class "Default")
      (node (ref "FT-POWERLED") (pin "A") (pinfunction "A_A") (pintype "passive"))
      (node (ref "FT232-R10") (pin "2") (pinfunction "2_2") (pintype "passive"))
      (node (ref "FT232USBCON") (pin "1") (pinfunction "1_1") (pintype "passive"))
      (node (ref "IC1") (pin "20") (pinfunction "VCC_20") (pintype "power_in"))
    )
    (net (code "99") (name "Net-(IC1-~{RESET})") (class "Default")
      (node (ref "FT232-R10") (pin "1") (pinfunction "1_1") (pintype "passive"))
      (node (ref "FT232-R11") (pin "2") (pinfunction "2_2") (pintype "passive"))
      (node (ref "IC1") (pin "19") (pinfunction "~{RESET}_19") (pintype "input"))
    )
    (net (code "100") (name "Net-(IC2-I1)") (class "Default")
      (node (ref "IC2") (pin "1") (pinfunction "I1_1") (pintype "input"))
      (node (ref "U1") (pin "78") (pinfunction "PK3_78") (pintype "bidirectional"))
    )
    (net (code "101") (name "Net-(IC2-I2)") (class "Default")
      (node (ref "IC2") (pin "2") (pinfunction "I2_2") (pintype "input"))
      (node (ref "U1") (pin "77") (pinfunction "PK2_77") (pintype "bidirectional"))
    )
    (net (code "102") (name "Net-(IC2-I3)") (class "Default")
      (node (ref "IC2") (pin "3") (pinfunction "I3_3") (pintype "input"))
      (node (ref "U1") (pin "76") (pinfunction "PK1_76") (pintype "bidirectional"))
    )
    (net (code "103") (name "Net-(IC2-I4)") (class "Default")
      (node (ref "IC2") (pin "4") (pinfunction "I4_4") (pintype "input"))
      (node (ref "U1") (pin "75") (pinfunction "PK0_75") (pintype "bidirectional"))
    )
    (net (code "104") (name "Net-(IC2-O1)") (class "Default")
      (node (ref "IC2") (pin "16") (pinfunction "O1_16") (pintype "open_collector"))
      (node (ref "J1") (pin "P$2") (pinfunction "2_P$2") (pintype "bidirectional"))
      (node (ref "STEPINDI1") (pin "C") (pinfunction "C_C") (pintype "passive"))
    )
    (net (code "105") (name "Net-(IC2-O2)") (class "Default")
      (node (ref "IC2") (pin "15") (pinfunction "O2_15") (pintype "open_collector"))
      (node (ref "J1") (pin "P$3") (pinfunction "3_P$3") (pintype "bidirectional"))
      (node (ref "STEPINDI2") (pin "C") (pinfunction "C_C") (pintype "passive"))
    )
    (net (code "106") (name "Net-(IC2-O3)") (class "Default")
      (node (ref "IC2") (pin "14") (pinfunction "O3_14") (pintype "open_collector"))
      (node (ref "J1") (pin "P$4") (pinfunction "4_P$4") (pintype "bidirectional"))
      (node (ref "STEPINDI3") (pin "C") (pinfunction "C_C") (pintype "passive"))
    )
    (net (code "107") (name "Net-(IC2-O4)") (class "Default")
      (node (ref "IC2") (pin "13") (pinfunction "O4_13") (pintype "open_collector"))
      (node (ref "J1") (pin "P$5") (pinfunction "5_P$5") (pintype "bidirectional"))
      (node (ref "STEPINDI4") (pin "C") (pinfunction "C_C") (pintype "passive"))
    )
    (net (code "108") (name "Net-(INDILED1-Pad1)") (class "Default")
      (node (ref "INDILED1") (pin "1") (pinfunction "1_1") (pintype "passive"))
      (node (ref "STEPINDI1") (pin "A") (pinfunction "A_A") (pintype "passive"))
    )
    (net (code "109") (name "Net-(INDILED2-Pad1)") (class "Default")
      (node (ref "INDILED2") (pin "1") (pinfunction "1_1") (pintype "passive"))
      (node (ref "STEPINDI2") (pin "A") (pinfunction "A_A") (pintype "passive"))
    )
    (net (code "110") (name "Net-(INDILED3-Pad1)") (class "Default")
      (node (ref "INDILED3") (pin "1") (pinfunction "1_1") (pintype "passive"))
      (node (ref "STEPINDI3") (pin "A") (pinfunction "A_A") (pintype "passive"))
    )
    (net (code "111") (name "Net-(INDILED4-Pad1)") (class "Default")
      (node (ref "INDILED4") (pin "1") (pinfunction "1_1") (pintype "passive"))
      (node (ref "STEPINDI4") (pin "A") (pinfunction "A_A") (pintype "passive"))
    )
    (net (code "112") (name "Net-(L3-C)") (class "Default")
      (node (ref "ERROR1-R") (pin "2") (pinfunction "2_2") (pintype "passive"))
      (node (ref "L3") (pin "K") (pinfunction "C_K") (pintype "passive"))
    )
    (net (code "113") (name "Net-(L4-C)") (class "Default")
      (node (ref "ERROR2-R") (pin "2") (pinfunction "2_2") (pintype "passive"))
      (node (ref "L4") (pin "K") (pinfunction "C_K") (pintype "passive"))
    )
    (net (code "114") (name "Net-(M-SW-O)") (class "Default")
      (node (ref "M-SW") (pin "1") (pinfunction "O_1") (pintype "passive"))
      (node (ref "SP-R5") (pin "1") (pinfunction "1_1") (pintype "passive"))
    )
    (net (code "115") (name "Net-(M-SW-P)") (class "Default")
      (node (ref "M-SW") (pin "2") (pinfunction "P_2") (pintype "passive"))
      (node (ref "Q4") (pin "G") (pinfunction "G_G") (pintype "passive"))
    )
    (net (code "116") (name "Net-(MEGA1-PB6(XTAL1{slash}TOSC1))") (class "Default")
      (node (ref "MEGA1") (pin "7") (pinfunction "PB6(XTAL1/TOSC1)_7") (pintype "bidirectional"))
      (node (ref "Q1") (pin "1") (pinfunction "1_1") (pintype "output"))
    )
    (net (code "117") (name "Net-(MEGA1-PB7(XTAL2{slash}TOSC2))") (class "Default")
      (node (ref "MEGA1") (pin "8") (pinfunction "PB7(XTAL2/TOSC2)_8") (pintype "bidirectional"))
      (node (ref "Q1") (pin "3") (pinfunction "3_3") (pintype "input"))
    )
    (net (code "118") (name "Net-(MEGA2-PB6(XTAL1{slash}TOSC1))") (class "Default")
      (node (ref "MEGA2") (pin "7") (pinfunction "PB6(XTAL1/TOSC1)_7") (pintype "bidirectional"))
      (node (ref "Q2") (pin "1") (pinfunction "1_1") (pintype "output"))
    )
    (net (code "119") (name "Net-(MEGA2-PB7(XTAL2{slash}TOSC2))") (class "Default")
      (node (ref "MEGA2") (pin "8") (pinfunction "PB7(XTAL2/TOSC2)_8") (pintype "bidirectional"))
      (node (ref "Q2") (pin "3") (pinfunction "3_3") (pintype "input"))
    )
    (net (code "120") (name "Net-(Q3-PadS)") (class "Default")
      (node (ref "Q3") (pin "S") (pinfunction "S_S") (pintype "passive"))
      (node (ref "Q5") (pin "S") (pinfunction "S_S") (pintype "passive"))
      (node (ref "SP-R6") (pin "2") (pinfunction "2_2") (pintype "passive"))
    )
    (net (code "121") (name "Net-(S2-P)") (class "Default")
      (node (ref "S2") (pin "2") (pinfunction "P_2") (pintype "passive"))
      (node (ref "VOLTAGE-METER2") (pin "P$1") (pinfunction "1_P$1") (pintype "bidirectional"))
    )
    (net (code "122") (name "Net-(SL-R1-Pad2)") (class "Default")
      (node (ref "SL-R1") (pin "2") (pinfunction "2_2") (pintype "passive"))
      (node (ref "SP-LED") (pin "C") (pinfunction "C_C") (pintype "passive"))
    )
    (net (code "123") (name "Net-(SP-RC1-A)") (class "Default")
      (node (ref "SP-R1") (pin "2") (pinfunction "2_2") (pintype "passive"))
      (node (ref "SP-RC1") (pin "1") (pinfunction "A_1") (pintype "passive"))
      (node (ref "SP-RC1") (pin "2") (pinfunction "S_2") (pintype "passive"))
    )
    (net (code "124") (name "Net-(SP-RC2-A)") (class "Default")
      (node (ref "SP-R3") (pin "2") (pinfunction "2_2") (pintype "passive"))
      (node (ref "SP-RC2") (pin "1") (pinfunction "A_1") (pintype "passive"))
      (node (ref "SP-RC2") (pin "2") (pinfunction "S_2") (pintype "passive"))
    )
    (net (code "125") (name "Net-(SUOPPLY-SW2-1)") (class "Default")
      (node (ref "MAINSW2") (pin "1") (pinfunction "1_1") (pintype "passive"))
      (node (ref "Q5") (pin "G") (pinfunction "G_G") (pintype "passive"))
      (node (ref "SP-R6") (pin "1") (pinfunction "1_1") (pintype "passive"))
      (node (ref "SUOPPLY-SW2") (pin "P$1") (pinfunction "1_P$1") (pintype "bidirectional"))
    )
    (net (code "126") (name "Net-(SUPPLY9A-KL)") (class "Default")
      (node (ref "Q3") (pin "D") (pinfunction "D_D") (pintype "passive"))
      (node (ref "SUPPLY9") (pin "1") (pinfunction "KL_1") (pintype "passive"))
      (node (ref "X2") (pin "1") (pinfunction "1_1") (pintype "passive"))
    )
    (net (code "127") (name "Net-(U$2A-S)") (class "Default")
      (node (ref "Q4") (pin "D") (pinfunction "D_D") (pintype "passive"))
      (node (ref "U$2") (pin "1") (pinfunction "S_1") (pintype "passive"))
    )
    (net (code "128") (name "Net-(U1-PDI)") (class "Default")
      (node (ref "SV1") (pin "1") (pinfunction "1_1") (pintype "passive"))
      (node (ref "U1") (pin "89") (pinfunction "PDI_89") (pintype "bidirectional"))
    )
    (net (code "129") (name "unconnected-(3.3REG-NC_1-Pad8)") (class "Default")
      (node (ref "3.3REG") (pin "8") (pinfunction "NC_1_8") (pintype "bidirectional"))
    )
    (net (code "130") (name "unconnected-(3.3REG-NC_2-Pad11)") (class "Default")
      (node (ref "3.3REG") (pin "11") (pinfunction "NC_2_11") (pintype "bidirectional"))
    )
    (net (code "131") (name "unconnected-(3.3REG-NC_3-Pad12)") (class "Default")
      (node (ref "3.3REG") (pin "12") (pinfunction "NC_3_12") (pintype "bidirectional"))
    )
    (net (code "132") (name "unconnected-(3.3REG-PGOOD-Pad10)") (class "Default")
      (node (ref "3.3REG") (pin "10") (pinfunction "PGOOD_10") (pintype "bidirectional"))
    )
    (net (code "133") (name "unconnected-(3.3REG-SEQ-Pad9)") (class "Default")
      (node (ref "3.3REG") (pin "9") (pinfunction "SEQ_9") (pintype "bidirectional"))
    )
    (net (code "134") (name "unconnected-(5VREG-NC_1-Pad8)") (class "Default")
      (node (ref "5VREG") (pin "8") (pinfunction "NC_1_8") (pintype "bidirectional"))
    )
    (net (code "135") (name "unconnected-(5VREG-NC_2-Pad11)") (class "Default")
      (node (ref "5VREG") (pin "11") (pinfunction "NC_2_11") (pintype "bidirectional"))
    )
    (net (code "136") (name "unconnected-(5VREG-NC_3-Pad12)") (class "Default")
      (node (ref "5VREG") (pin "12") (pinfunction "NC_3_12") (pintype "bidirectional"))
    )
    (net (code "137") (name "unconnected-(5VREG-PGOOD-Pad10)") (class "Default")
      (node (ref "5VREG") (pin "10") (pinfunction "PGOOD_10") (pintype "bidirectional"))
    )
    (net (code "138") (name "unconnected-(5VREG-SEQ-Pad9)") (class "Default")
      (node (ref "5VREG") (pin "9") (pinfunction "SEQ_9") (pintype "bidirectional"))
    )
    (net (code "139") (name "unconnected-(FT232USBCON-Pad4)") (class "Default")
      (node (ref "FT232USBCON") (pin "4") (pinfunction "4_4") (pintype "passive"))
    )
    (net (code "140") (name "unconnected-(IC1-CBUS0-Pad23)") (class "Default")
      (node (ref "IC1") (pin "23") (pinfunction "CBUS0_23") (pintype "bidirectional"))
    )
    (net (code "141") (name "unconnected-(IC1-CBUS1-Pad22)") (class "Default")
      (node (ref "IC1") (pin "22") (pinfunction "CBUS1_22") (pintype "bidirectional"))
    )
    (net (code "142") (name "unconnected-(IC1-CBUS2-Pad13)") (class "Default")
      (node (ref "IC1") (pin "13") (pinfunction "CBUS2_13") (pintype "bidirectional"))
    )
    (net (code "143") (name "unconnected-(IC1-CBUS3-Pad14)") (class "Default")
      (node (ref "IC1") (pin "14") (pinfunction "CBUS3_14") (pintype "bidirectional"))
    )
    (net (code "144") (name "unconnected-(IC1-CBUS4-Pad12)") (class "Default")
      (node (ref "IC1") (pin "12") (pinfunction "CBUS4_12") (pintype "bidirectional"))
    )
    (net (code "145") (name "unconnected-(IC1-OSCI-Pad27)") (class "Default")
      (node (ref "IC1") (pin "27") (pinfunction "OSCI_27") (pintype "input"))
    )
    (net (code "146") (name "unconnected-(IC1-OSCO-Pad28)") (class "Default")
      (node (ref "IC1") (pin "28") (pinfunction "OSCO_28") (pintype "output"))
    )
    (net (code "147") (name "unconnected-(IC1-~{DTR}-Pad2)") (class "Default")
      (node (ref "IC1") (pin "2") (pinfunction "~{DTR}_2") (pintype "output"))
    )
    (net (code "148") (name "unconnected-(IC1-~{RTS}-Pad3)") (class "Default")
      (node (ref "IC1") (pin "3") (pinfunction "~{RTS}_3") (pintype "output"))
    )
    (net (code "149") (name "unconnected-(IC2-O5-Pad12)") (class "Default")
      (node (ref "IC2") (pin "12") (pinfunction "O5_12") (pintype "open_collector"))
    )
    (net (code "150") (name "unconnected-(IC2-O6-Pad11)") (class "Default")
      (node (ref "IC2") (pin "11") (pinfunction "O6_11") (pintype "open_collector"))
    )
    (net (code "151") (name "unconnected-(IC2-O7-Pad10)") (class "Default")
      (node (ref "IC2") (pin "10") (pinfunction "O7_10") (pintype "open_collector"))
    )
    (net (code "152") (name "unconnected-(JTAG-Pad7)") (class "Default")
      (node (ref "JTAG") (pin "7") (pinfunction "7_7") (pintype "passive"))
    )
    (net (code "153") (name "unconnected-(JTAG-Pad8)") (class "Default")
      (node (ref "JTAG") (pin "8") (pinfunction "8_8") (pintype "passive"))
    )
    (net (code "154") (name "unconnected-(MAINSW2-Pad3)") (class "Default")
      (node (ref "MAINSW2") (pin "3") (pinfunction "3_3") (pintype "passive"))
    )
    (net (code "155") (name "unconnected-(MEGA1-ADC6-Pad19)") (class "Default")
      (node (ref "MEGA1") (pin "19") (pinfunction "ADC6_19") (pintype "bidirectional"))
    )
    (net (code "156") (name "unconnected-(MEGA1-ADC7-Pad22)") (class "Default")
      (node (ref "MEGA1") (pin "22") (pinfunction "ADC7_22") (pintype "bidirectional"))
    )
    (net (code "157") (name "unconnected-(MEGA1-PB0(ICP)-Pad12)") (class "Default")
      (node (ref "MEGA1") (pin "12") (pinfunction "PB0(ICP)_12") (pintype "bidirectional"))
    )
    (net (code "158") (name "unconnected-(MEGA1-PB1(OC1A)-Pad13)") (class "Default")
      (node (ref "MEGA1") (pin "13") (pinfunction "PB1(OC1A)_13") (pintype "bidirectional"))
    )
    (net (code "159") (name "unconnected-(MEGA1-PC0(ADC0)-Pad23)") (class "Default")
      (node (ref "MEGA1") (pin "23") (pinfunction "PC0(ADC0)_23") (pintype "bidirectional"))
    )
    (net (code "160") (name "unconnected-(MEGA1-PC1(ADC1)-Pad24)") (class "Default")
      (node (ref "MEGA1") (pin "24") (pinfunction "PC1(ADC1)_24") (pintype "bidirectional"))
    )
    (net (code "161") (name "unconnected-(MEGA1-PD4(XCK{slash}T0)-Pad2)") (class "Default")
      (node (ref "MEGA1") (pin "2") (pinfunction "PD4(XCK/T0)_2") (pintype "bidirectional"))
    )
    (net (code "162") (name "unconnected-(MEGA1-PD5(T1)-Pad9)") (class "Default")
      (node (ref "MEGA1") (pin "9") (pinfunction "PD5(T1)_9") (pintype "bidirectional"))
    )
    (net (code "163") (name "unconnected-(MEGA1-PD7(AIN1)-Pad11)") (class "Default")
      (node (ref "MEGA1") (pin "11") (pinfunction "PD7(AIN1)_11") (pintype "bidirectional"))
    )
    (net (code "164") (name "unconnected-(MEGA2-ADC6-Pad19)") (class "Default")
      (node (ref "MEGA2") (pin "19") (pinfunction "ADC6_19") (pintype "bidirectional"))
    )
    (net (code "165") (name "unconnected-(MEGA2-ADC7-Pad22)") (class "Default")
      (node (ref "MEGA2") (pin "22") (pinfunction "ADC7_22") (pintype "bidirectional"))
    )
    (net (code "166") (name "unconnected-(MEGA2-PB0(ICP)-Pad12)") (class "Default")
      (node (ref "MEGA2") (pin "12") (pinfunction "PB0(ICP)_12") (pintype "bidirectional"))
    )
    (net (code "167") (name "unconnected-(MEGA2-PB1(OC1A)-Pad13)") (class "Default")
      (node (ref "MEGA2") (pin "13") (pinfunction "PB1(OC1A)_13") (pintype "bidirectional"))
    )
    (net (code "168") (name "unconnected-(MEGA2-PC0(ADC0)-Pad23)") (class "Default")
      (node (ref "MEGA2") (pin "23") (pinfunction "PC0(ADC0)_23") (pintype "bidirectional"))
    )
    (net (code "169") (name "unconnected-(MEGA2-PC1(ADC1)-Pad24)") (class "Default")
      (node (ref "MEGA2") (pin "24") (pinfunction "PC1(ADC1)_24") (pintype "bidirectional"))
    )
    (net (code "170") (name "unconnected-(MEGA2-PD4(XCK{slash}T0)-Pad2)") (class "Default")
      (node (ref "MEGA2") (pin "2") (pinfunction "PD4(XCK/T0)_2") (pintype "bidirectional"))
    )
    (net (code "171") (name "unconnected-(MEGA2-PD5(T1)-Pad9)") (class "Default")
      (node (ref "MEGA2") (pin "9") (pinfunction "PD5(T1)_9") (pintype "bidirectional"))
    )
    (net (code "172") (name "unconnected-(MEGA2-PD7(AIN1)-Pad11)") (class "Default")
      (node (ref "MEGA2") (pin "11") (pinfunction "PD7(AIN1)_11") (pintype "bidirectional"))
    )
    (net (code "173") (name "unconnected-(MOTORDRIVER-Pad12)") (class "Default")
      (node (ref "MOTORDRIVER") (pin "12") (pinfunction "12_12") (pintype "passive"))
    )
    (net (code "174") (name "unconnected-(MOTORDRIVER-Pad14)") (class "Default")
      (node (ref "MOTORDRIVER") (pin "14") (pinfunction "14_14") (pintype "passive"))
    )
    (net (code "175") (name "unconnected-(SUOPPLY-SW2-3-PadP$3)") (class "Default")
      (node (ref "SUOPPLY-SW2") (pin "P$3") (pinfunction "3_P$3") (pintype "bidirectional"))
    )
    (net (code "176") (name "unconnected-(SV1-Pad3)") (class "Default")
      (node (ref "SV1") (pin "3") (pinfunction "3_3") (pintype "passive"))
    )
    (net (code "177") (name "unconnected-(SV1-Pad4)") (class "Default")
      (node (ref "SV1") (pin "4") (pinfunction "4_4") (pintype "passive"))
    )
    (net (code "178") (name "unconnected-(TO-UNDER-Pad22)") (class "Default")
      (node (ref "TO-UNDER") (pin "22") (pinfunction "22_22") (pintype "passive"))
    )
    (net (code "179") (name "unconnected-(TO-UNDER-Pad23)") (class "Default")
      (node (ref "TO-UNDER") (pin "23") (pinfunction "23_23") (pintype "passive"))
    )
    (net (code "180") (name "unconnected-(TWILITE-Pad1)") (class "Default")
      (node (ref "TWILITE") (pin "1") (pinfunction "1_1") (pintype "passive"))
    )
    (net (code "181") (name "unconnected-(TWILITE-Pad3)") (class "Default")
      (node (ref "TWILITE") (pin "3") (pinfunction "3_3") (pintype "passive"))
    )
    (net (code "182") (name "unconnected-(TWILITE-Pad5)") (class "Default")
      (node (ref "TWILITE") (pin "5") (pinfunction "5_5") (pintype "passive"))
    )
    (net (code "183") (name "unconnected-(U1-PA1-Pad96)") (class "Default")
      (node (ref "U1") (pin "96") (pinfunction "PA1_96") (pintype "bidirectional"))
    )
    (net (code "184") (name "unconnected-(U1-PA2-Pad97)") (class "Default")
      (node (ref "U1") (pin "97") (pinfunction "PA2_97") (pintype "bidirectional"))
    )
    (net (code "185") (name "unconnected-(U1-PA3-Pad98)") (class "Default")
      (node (ref "U1") (pin "98") (pinfunction "PA3_98") (pintype "bidirectional"))
    )
    (net (code "186") (name "unconnected-(U1-PA4-Pad99)") (class "Default")
      (node (ref "U1") (pin "99") (pinfunction "PA4_99") (pintype "bidirectional"))
    )
    (net (code "187") (name "unconnected-(U1-PA5-Pad100)") (class "Default")
      (node (ref "U1") (pin "100") (pinfunction "PA5_100") (pintype "bidirectional"))
    )
    (net (code "188") (name "unconnected-(U1-PA6-Pad1)") (class "Default")
      (node (ref "U1") (pin "1") (pinfunction "PA6_1") (pintype "bidirectional"))
    )
    (net (code "189") (name "unconnected-(U1-PA7-Pad2)") (class "Default")
      (node (ref "U1") (pin "2") (pinfunction "PA7_2") (pintype "bidirectional"))
    )
    (net (code "190") (name "unconnected-(U1-PC4-Pad19)") (class "Default")
      (node (ref "U1") (pin "19") (pinfunction "PC4_19") (pintype "bidirectional"))
    )
    (net (code "191") (name "unconnected-(U1-PE6-Pad41)") (class "Default")
      (node (ref "U1") (pin "41") (pinfunction "PE6_41") (pintype "bidirectional"))
    )
    (net (code "192") (name "unconnected-(U1-PE7-Pad42)") (class "Default")
      (node (ref "U1") (pin "42") (pinfunction "PE7_42") (pintype "bidirectional"))
    )
    (net (code "193") (name "unconnected-(U1-PH3-Pad58)") (class "Default")
      (node (ref "U1") (pin "58") (pinfunction "PH3_58") (pintype "bidirectional"))
    )
    (net (code "194") (name "unconnected-(U1-PH4-Pad59)") (class "Default")
      (node (ref "U1") (pin "59") (pinfunction "PH4_59") (pintype "bidirectional"))
    )
    (net (code "195") (name "unconnected-(U1-PH5-Pad60)") (class "Default")
      (node (ref "U1") (pin "60") (pinfunction "PH5_60") (pintype "bidirectional"))
    )
    (net (code "196") (name "unconnected-(U1-PH6-Pad61)") (class "Default")
      (node (ref "U1") (pin "61") (pinfunction "PH6_61") (pintype "bidirectional"))
    )
    (net (code "197") (name "unconnected-(U1-PH7-Pad62)") (class "Default")
      (node (ref "U1") (pin "62") (pinfunction "PH7_62") (pintype "bidirectional"))
    )
    (net (code "198") (name "unconnected-(U1-PJ2-Pad67)") (class "Default")
      (node (ref "U1") (pin "67") (pinfunction "PJ2_67") (pintype "bidirectional"))
    )
    (net (code "199") (name "unconnected-(U1-PJ3-Pad68)") (class "Default")
      (node (ref "U1") (pin "68") (pinfunction "PJ3_68") (pintype "bidirectional"))
    )
    (net (code "200") (name "unconnected-(U1-PJ4-Pad69)") (class "Default")
      (node (ref "U1") (pin "69") (pinfunction "PJ4_69") (pintype "bidirectional"))
    )
    (net (code "201") (name "unconnected-(U1-PK6-Pad81)") (class "Default")
      (node (ref "U1") (pin "81") (pinfunction "PK6_81") (pintype "bidirectional"))
    )
    (net (code "202") (name "unconnected-(U1-PQ3-Pad88)") (class "Default")
      (node (ref "U1") (pin "88") (pinfunction "PQ3_88") (pintype "bidirectional"))
    )
    (net (code "203") (name "unconnected-(U1-PR0-Pad91)") (class "Default")
      (node (ref "U1") (pin "91") (pinfunction "PR0_91") (pintype "bidirectional"))
    )
    (net (code "204") (name "unconnected-(U1-PR1-Pad92)") (class "Default")
      (node (ref "U1") (pin "92") (pinfunction "PR1_92") (pintype "bidirectional"))
    )
    (net (code "205") (name "unconnected-(X2-Pad3)") (class "Default")
      (node (ref "X2") (pin "3") (pinfunction "3_3") (pintype "passive"))
    )
  )
)
